# R210A.net
KiCad netlist of a schematic drawn in EAGLE
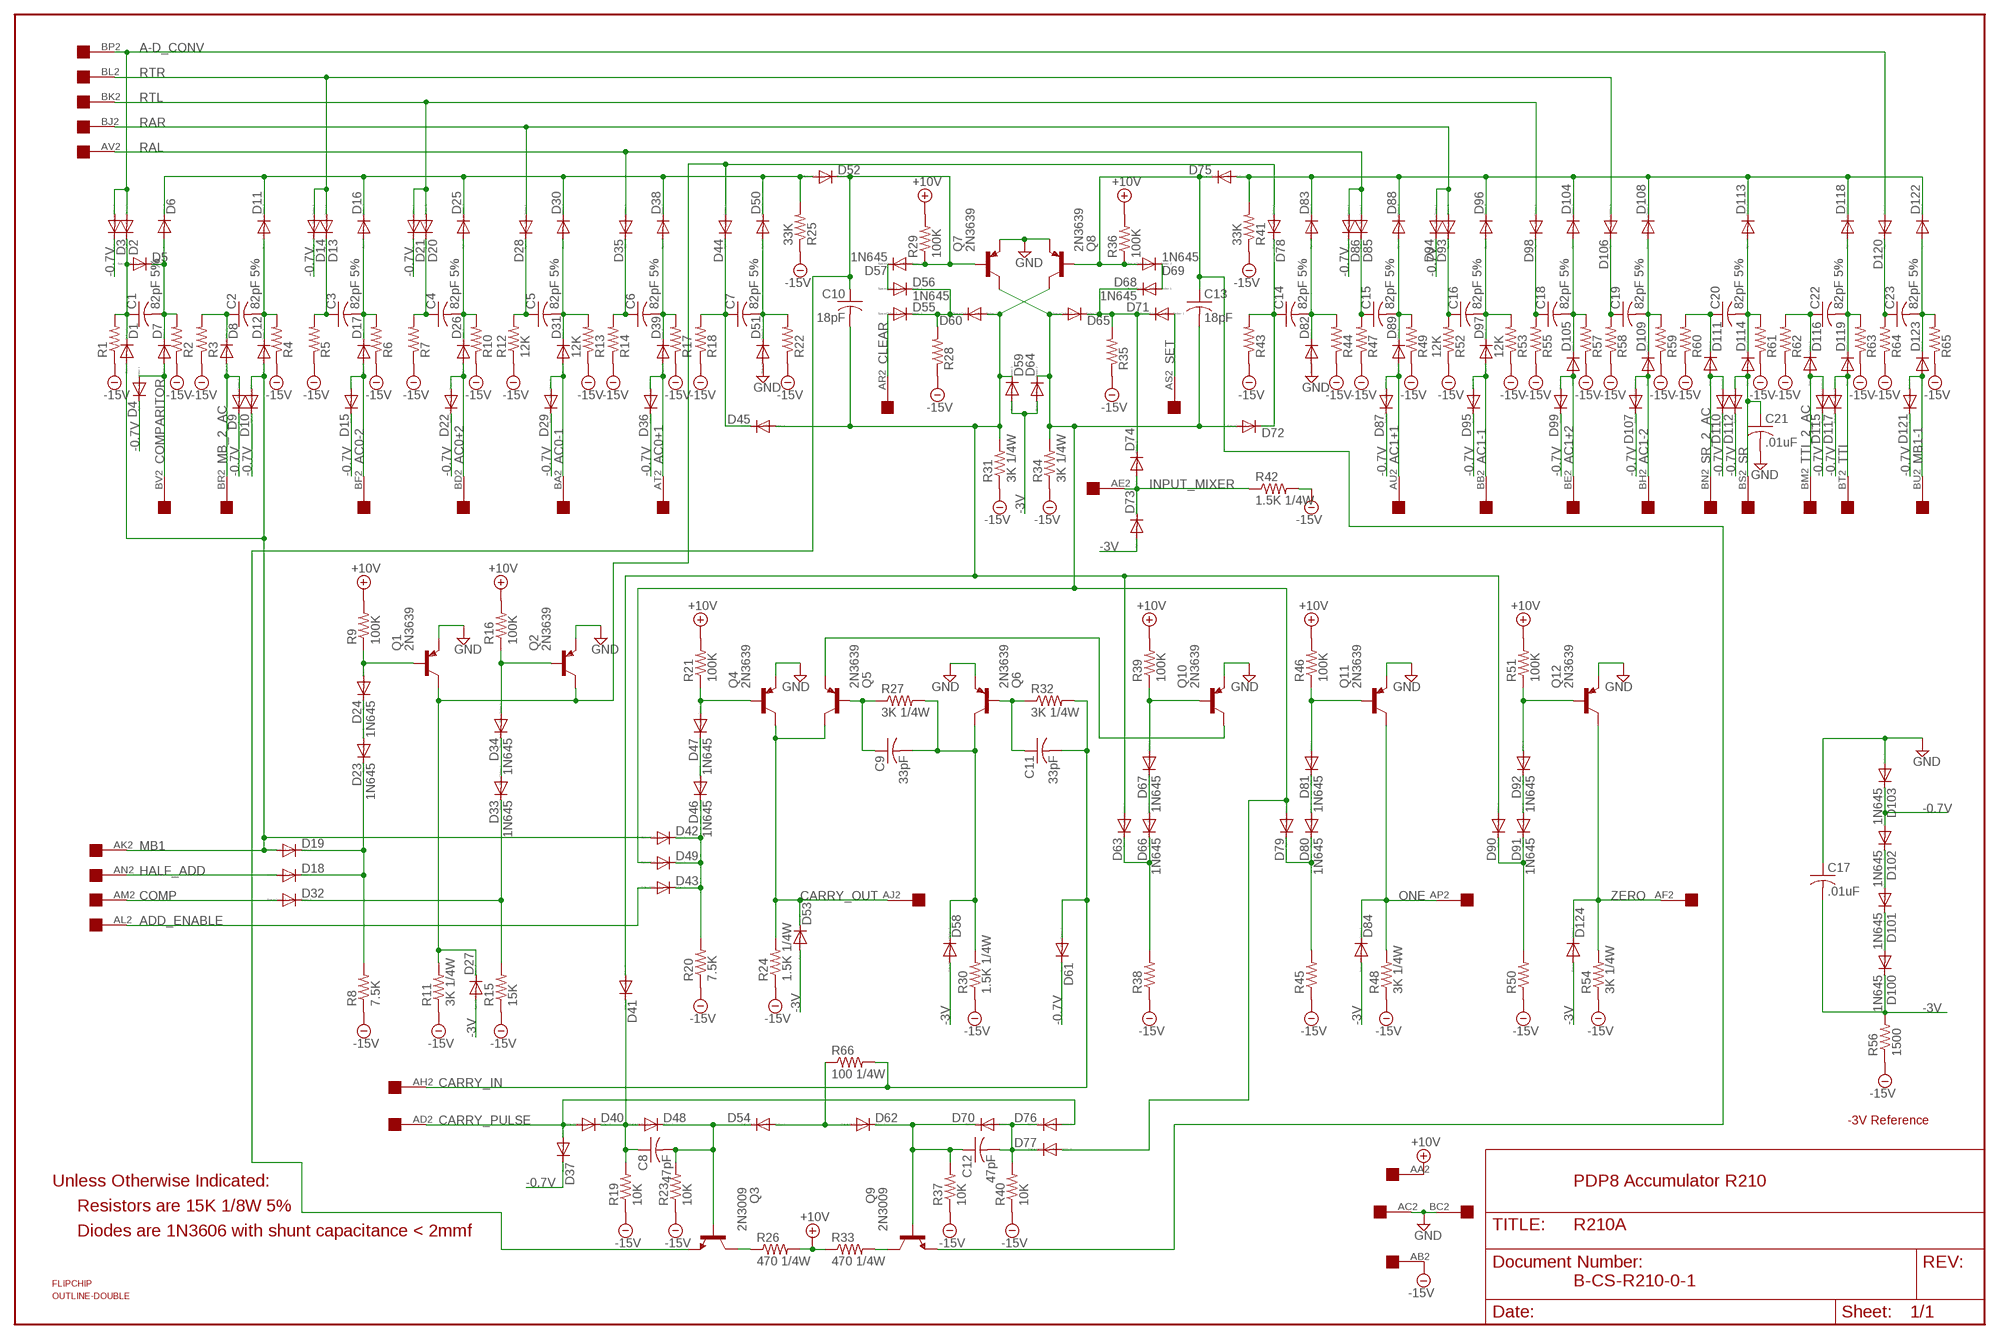
[diagram p0: schematic, sheet 1]

(export (version "E")
  (design (tool "Eeschema 10.0.6"))
  (components
    (comp (ref "C1")
      (value "82pF 5%")
      (footprint "eagle-import:C075-032X103")
      (libsource (lib "eagle-import") (part "C-US075-032X103"))
    )
    (comp (ref "C2")
      (value "82pF 5%")
      (footprint "eagle-import:C075-032X103")
      (libsource (lib "eagle-import") (part "C-US075-032X103"))
    )
    (comp (ref "C3")
      (value "82pF 5%")
      (footprint "eagle-import:C075-032X103")
      (libsource (lib "eagle-import") (part "C-US075-032X103"))
    )
    (comp (ref "C4")
      (value "82pF 5%")
      (footprint "eagle-import:C075-032X103")
      (libsource (lib "eagle-import") (part "C-US075-032X103"))
    )
    (comp (ref "C5")
      (value "82pF 5%")
      (footprint "eagle-import:C075-032X103")
      (libsource (lib "eagle-import") (part "C-US075-032X103"))
    )
    (comp (ref "C6")
      (value "82pF 5%")
      (footprint "eagle-import:C075-032X103")
      (libsource (lib "eagle-import") (part "C-US075-032X103"))
    )
    (comp (ref "C7")
      (value "82pF 5%")
      (footprint "eagle-import:C075-032X103")
      (libsource (lib "eagle-import") (part "C-US075-032X103"))
    )
    (comp (ref "C8")
      (value "47pF")
      (footprint "eagle-import:C075-032X103")
      (libsource (lib "eagle-import") (part "C-US075-032X103"))
    )
    (comp (ref "C9")
      (value "33pF")
      (footprint "eagle-import:C075-032X103")
      (libsource (lib "eagle-import") (part "C-US075-032X103"))
    )
    (comp (ref "C10")
      (value "18pF")
      (footprint "eagle-import:C075-032X103")
      (libsource (lib "eagle-import") (part "C-US075-032X103"))
    )
    (comp (ref "C11")
      (value "33pF")
      (footprint "eagle-import:C075-032X103")
      (libsource (lib "eagle-import") (part "C-US075-032X103"))
    )
    (comp (ref "C12")
      (value "47pF")
      (footprint "eagle-import:C075-032X103")
      (libsource (lib "eagle-import") (part "C-US075-032X103"))
    )
    (comp (ref "C13")
      (value "18pF")
      (footprint "eagle-import:C075-032X103")
      (libsource (lib "eagle-import") (part "C-US075-032X103"))
    )
    (comp (ref "C14")
      (value "82pF 5%")
      (footprint "eagle-import:C075-032X103")
      (libsource (lib "eagle-import") (part "C-US075-032X103"))
    )
    (comp (ref "C15")
      (value "82pF 5%")
      (footprint "eagle-import:C075-032X103")
      (libsource (lib "eagle-import") (part "C-US075-032X103"))
    )
    (comp (ref "C16")
      (value "82pF 5%")
      (footprint "eagle-import:C075-032X103")
      (libsource (lib "eagle-import") (part "C-US075-032X103"))
    )
    (comp (ref "C17")
      (value ".01uF")
      (footprint "eagle-import:C050-025X075")
      (libsource (lib "eagle-import") (part "C-US050-025X075"))
    )
    (comp (ref "C18")
      (value "82pF 5%")
      (footprint "eagle-import:C075-032X103")
      (libsource (lib "eagle-import") (part "C-US075-032X103"))
    )
    (comp (ref "C19")
      (value "82pF 5%")
      (footprint "eagle-import:C075-032X103")
      (libsource (lib "eagle-import") (part "C-US075-032X103"))
    )
    (comp (ref "C20")
      (value "82pF 5%")
      (footprint "eagle-import:C075-032X103")
      (libsource (lib "eagle-import") (part "C-US075-032X103"))
    )
    (comp (ref "C21")
      (value ".01uF")
      (footprint "eagle-import:C050-025X075")
      (libsource (lib "eagle-import") (part "C-US050-025X075"))
    )
    (comp (ref "C22")
      (value "82pF 5%")
      (footprint "eagle-import:C075-032X103")
      (libsource (lib "eagle-import") (part "C-US075-032X103"))
    )
    (comp (ref "C23")
      (value "82pF 5%")
      (footprint "eagle-import:C075-032X103")
      (libsource (lib "eagle-import") (part "C-US075-032X103"))
    )
    (comp (ref "D1")
      (value "1N4148DO35-10")
      (footprint "eagle-import:DO35-10")
      (libsource (lib "eagle-import") (part "1N4148DO35-10"))
    )
    (comp (ref "D2")
      (value "1N4148DO35-10")
      (footprint "eagle-import:DO35-10")
      (libsource (lib "eagle-import") (part "1N4148DO35-10"))
    )
    (comp (ref "D3")
      (value "1N4148DO35-10")
      (footprint "eagle-import:DO35-10")
      (libsource (lib "eagle-import") (part "1N4148DO35-10"))
    )
    (comp (ref "D4")
      (value "1N4148DO35-10")
      (footprint "eagle-import:DO35-10")
      (libsource (lib "eagle-import") (part "1N4148DO35-10"))
    )
    (comp (ref "D5")
      (value "1N4148DO35-10")
      (footprint "eagle-import:DO35-10")
      (libsource (lib "eagle-import") (part "1N4148DO35-10"))
    )
    (comp (ref "D6")
      (value "1N4148DO35-10")
      (footprint "eagle-import:DO35-10")
      (libsource (lib "eagle-import") (part "1N4148DO35-10"))
    )
    (comp (ref "D7")
      (value "1N4148DO35-10")
      (footprint "eagle-import:DO35-10")
      (libsource (lib "eagle-import") (part "1N4148DO35-10"))
    )
    (comp (ref "D8")
      (value "1N4148DO35-10")
      (footprint "eagle-import:DO35-10")
      (libsource (lib "eagle-import") (part "1N4148DO35-10"))
    )
    (comp (ref "D9")
      (value "1N4148DO35-10")
      (footprint "eagle-import:DO35-10")
      (libsource (lib "eagle-import") (part "1N4148DO35-10"))
    )
    (comp (ref "D10")
      (value "1N4148DO35-10")
      (footprint "eagle-import:DO35-10")
      (libsource (lib "eagle-import") (part "1N4148DO35-10"))
    )
    (comp (ref "D11")
      (value "1N4148DO35-10")
      (footprint "eagle-import:DO35-10")
      (libsource (lib "eagle-import") (part "1N4148DO35-10"))
    )
    (comp (ref "D12")
      (value "1N4148DO35-10")
      (footprint "eagle-import:DO35-10")
      (libsource (lib "eagle-import") (part "1N4148DO35-10"))
    )
    (comp (ref "D13")
      (value "1N4148DO35-10")
      (footprint "eagle-import:DO35-10")
      (libsource (lib "eagle-import") (part "1N4148DO35-10"))
    )
    (comp (ref "D14")
      (value "1N4148DO35-10")
      (footprint "eagle-import:DO35-10")
      (libsource (lib "eagle-import") (part "1N4148DO35-10"))
    )
    (comp (ref "D15")
      (value "1N4148DO35-10")
      (footprint "eagle-import:DO35-10")
      (libsource (lib "eagle-import") (part "1N4148DO35-10"))
    )
    (comp (ref "D16")
      (value "1N4148DO35-10")
      (footprint "eagle-import:DO35-10")
      (libsource (lib "eagle-import") (part "1N4148DO35-10"))
    )
    (comp (ref "D17")
      (value "1N4148DO35-10")
      (footprint "eagle-import:DO35-10")
      (libsource (lib "eagle-import") (part "1N4148DO35-10"))
    )
    (comp (ref "D18")
      (value "1N4148DO35-10")
      (footprint "eagle-import:DO35-10")
      (libsource (lib "eagle-import") (part "1N4148DO35-10"))
    )
    (comp (ref "D19")
      (value "1N4148DO35-10")
      (footprint "eagle-import:DO35-10")
      (libsource (lib "eagle-import") (part "1N4148DO35-10"))
    )
    (comp (ref "D20")
      (value "1N4148DO35-10")
      (footprint "eagle-import:DO35-10")
      (libsource (lib "eagle-import") (part "1N4148DO35-10"))
    )
    (comp (ref "D21")
      (value "1N4148DO35-10")
      (footprint "eagle-import:DO35-10")
      (libsource (lib "eagle-import") (part "1N4148DO35-10"))
    )
    (comp (ref "D22")
      (value "1N4148DO35-10")
      (footprint "eagle-import:DO35-10")
      (libsource (lib "eagle-import") (part "1N4148DO35-10"))
    )
    (comp (ref "D23")
      (value "1N645")
      (footprint "eagle-import:DO35-10")
      (libsource (lib "eagle-import") (part "1N4148DO35-10"))
    )
    (comp (ref "D24")
      (value "1N645")
      (footprint "eagle-import:DO35-10")
      (libsource (lib "eagle-import") (part "1N4148DO35-10"))
    )
    (comp (ref "D25")
      (value "1N4148DO35-10")
      (footprint "eagle-import:DO35-10")
      (libsource (lib "eagle-import") (part "1N4148DO35-10"))
    )
    (comp (ref "D26")
      (value "1N4148DO35-10")
      (footprint "eagle-import:DO35-10")
      (libsource (lib "eagle-import") (part "1N4148DO35-10"))
    )
    (comp (ref "D27")
      (value "1N4148DO35-10")
      (footprint "eagle-import:DO35-10")
      (libsource (lib "eagle-import") (part "1N4148DO35-10"))
    )
    (comp (ref "D28")
      (value "1N4148DO35-10")
      (footprint "eagle-import:DO35-10")
      (libsource (lib "eagle-import") (part "1N4148DO35-10"))
    )
    (comp (ref "D29")
      (value "1N4148DO35-10")
      (footprint "eagle-import:DO35-10")
      (libsource (lib "eagle-import") (part "1N4148DO35-10"))
    )
    (comp (ref "D30")
      (value "1N4148DO35-10")
      (footprint "eagle-import:DO35-10")
      (libsource (lib "eagle-import") (part "1N4148DO35-10"))
    )
    (comp (ref "D31")
      (value "1N4148DO35-10")
      (footprint "eagle-import:DO35-10")
      (libsource (lib "eagle-import") (part "1N4148DO35-10"))
    )
    (comp (ref "D32")
      (value "1N4148DO35-10")
      (footprint "eagle-import:DO35-10")
      (libsource (lib "eagle-import") (part "1N4148DO35-10"))
    )
    (comp (ref "D33")
      (value "1N645")
      (footprint "eagle-import:DO35-10")
      (libsource (lib "eagle-import") (part "1N4148DO35-10"))
    )
    (comp (ref "D34")
      (value "1N645")
      (footprint "eagle-import:DO35-10")
      (libsource (lib "eagle-import") (part "1N4148DO35-10"))
    )
    (comp (ref "D35")
      (value "1N4148DO35-10")
      (footprint "eagle-import:DO35-10")
      (libsource (lib "eagle-import") (part "1N4148DO35-10"))
    )
    (comp (ref "D36")
      (value "1N4148DO35-10")
      (footprint "eagle-import:DO35-10")
      (libsource (lib "eagle-import") (part "1N4148DO35-10"))
    )
    (comp (ref "D37")
      (value "1N4148DO35-10")
      (footprint "eagle-import:DO35-10")
      (libsource (lib "eagle-import") (part "1N4148DO35-10"))
    )
    (comp (ref "D38")
      (value "1N4148DO35-10")
      (footprint "eagle-import:DO35-10")
      (libsource (lib "eagle-import") (part "1N4148DO35-10"))
    )
    (comp (ref "D39")
      (value "1N4148DO35-10")
      (footprint "eagle-import:DO35-10")
      (libsource (lib "eagle-import") (part "1N4148DO35-10"))
    )
    (comp (ref "D40")
      (value "1N4148DO35-10")
      (footprint "eagle-import:DO35-10")
      (libsource (lib "eagle-import") (part "1N4148DO35-10"))
    )
    (comp (ref "D41")
      (value "1N4148DO35-10")
      (footprint "eagle-import:DO35-10")
      (libsource (lib "eagle-import") (part "1N4148DO35-10"))
    )
    (comp (ref "D42")
      (value "1N4148DO35-10")
      (footprint "eagle-import:DO35-10")
      (libsource (lib "eagle-import") (part "1N4148DO35-10"))
    )
    (comp (ref "D43")
      (value "1N4148DO35-10")
      (footprint "eagle-import:DO35-10")
      (libsource (lib "eagle-import") (part "1N4148DO35-10"))
    )
    (comp (ref "D44")
      (value "1N4148DO35-10")
      (footprint "eagle-import:DO35-10")
      (libsource (lib "eagle-import") (part "1N4148DO35-10"))
    )
    (comp (ref "D45")
      (value "1N4148DO35-10")
      (footprint "eagle-import:DO35-10")
      (libsource (lib "eagle-import") (part "1N4148DO35-10"))
    )
    (comp (ref "D46")
      (value "1N645")
      (footprint "eagle-import:DO35-10")
      (libsource (lib "eagle-import") (part "1N4148DO35-10"))
    )
    (comp (ref "D47")
      (value "1N645")
      (footprint "eagle-import:DO35-10")
      (libsource (lib "eagle-import") (part "1N4148DO35-10"))
    )
    (comp (ref "D48")
      (value "1N4148DO35-10")
      (footprint "eagle-import:DO35-10")
      (libsource (lib "eagle-import") (part "1N4148DO35-10"))
    )
    (comp (ref "D49")
      (value "1N4148DO35-10")
      (footprint "eagle-import:DO35-10")
      (libsource (lib "eagle-import") (part "1N4148DO35-10"))
    )
    (comp (ref "D50")
      (value "1N4148DO35-10")
      (footprint "eagle-import:DO35-10")
      (libsource (lib "eagle-import") (part "1N4148DO35-10"))
    )
    (comp (ref "D51")
      (value "1N4148DO35-10")
      (footprint "eagle-import:DO35-10")
      (libsource (lib "eagle-import") (part "1N4148DO35-10"))
    )
    (comp (ref "D52")
      (value "1N4148DO35-10")
      (footprint "eagle-import:DO35-10")
      (libsource (lib "eagle-import") (part "1N4148DO35-10"))
    )
    (comp (ref "D53")
      (value "1N4148DO35-10")
      (footprint "eagle-import:DO35-10")
      (libsource (lib "eagle-import") (part "1N4148DO35-10"))
    )
    (comp (ref "D54")
      (value "1N4148DO35-10")
      (footprint "eagle-import:DO35-10")
      (libsource (lib "eagle-import") (part "1N4148DO35-10"))
    )
    (comp (ref "D55")
      (value "1N4148DO35-10")
      (footprint "eagle-import:DO35-10")
      (libsource (lib "eagle-import") (part "1N4148DO35-10"))
    )
    (comp (ref "D56")
      (value "1N645")
      (footprint "eagle-import:DO35-10")
      (libsource (lib "eagle-import") (part "1N4148DO35-10"))
    )
    (comp (ref "D57")
      (value "1N645")
      (footprint "eagle-import:DO35-10")
      (libsource (lib "eagle-import") (part "1N4148DO35-10"))
    )
    (comp (ref "D58")
      (value "1N4148DO35-10")
      (footprint "eagle-import:DO35-10")
      (libsource (lib "eagle-import") (part "1N4148DO35-10"))
    )
    (comp (ref "D59")
      (value "1N4148DO35-10")
      (footprint "eagle-import:DO35-10")
      (libsource (lib "eagle-import") (part "1N4148DO35-10"))
    )
    (comp (ref "D60")
      (value "1N4148DO35-10")
      (footprint "eagle-import:DO35-10")
      (libsource (lib "eagle-import") (part "1N4148DO35-10"))
    )
    (comp (ref "D61")
      (value "1N4148DO35-10")
      (footprint "eagle-import:DO35-10")
      (libsource (lib "eagle-import") (part "1N4148DO35-10"))
    )
    (comp (ref "D62")
      (value "1N4148DO35-10")
      (footprint "eagle-import:DO35-10")
      (libsource (lib "eagle-import") (part "1N4148DO35-10"))
    )
    (comp (ref "D63")
      (value "1N4148DO35-10")
      (footprint "eagle-import:DO35-10")
      (libsource (lib "eagle-import") (part "1N4148DO35-10"))
    )
    (comp (ref "D64")
      (value "1N4148DO35-10")
      (footprint "eagle-import:DO35-10")
      (libsource (lib "eagle-import") (part "1N4148DO35-10"))
    )
    (comp (ref "D65")
      (value "1N4148DO35-10")
      (footprint "eagle-import:DO35-10")
      (libsource (lib "eagle-import") (part "1N4148DO35-10"))
    )
    (comp (ref "D66")
      (value "1N645")
      (footprint "eagle-import:DO35-10")
      (libsource (lib "eagle-import") (part "1N4148DO35-10"))
    )
    (comp (ref "D67")
      (value "1N645")
      (footprint "eagle-import:DO35-10")
      (libsource (lib "eagle-import") (part "1N4148DO35-10"))
    )
    (comp (ref "D68")
      (value "1N645")
      (footprint "eagle-import:DO35-10")
      (libsource (lib "eagle-import") (part "1N4148DO35-10"))
    )
    (comp (ref "D69")
      (value "1N645")
      (footprint "eagle-import:DO35-10")
      (libsource (lib "eagle-import") (part "1N4148DO35-10"))
    )
    (comp (ref "D70")
      (value "1N4148DO35-10")
      (footprint "eagle-import:DO35-10")
      (libsource (lib "eagle-import") (part "1N4148DO35-10"))
    )
    (comp (ref "D71")
      (value "1N4148DO35-10")
      (footprint "eagle-import:DO35-10")
      (libsource (lib "eagle-import") (part "1N4148DO35-10"))
    )
    (comp (ref "D72")
      (value "1N4148DO35-10")
      (footprint "eagle-import:DO35-10")
      (libsource (lib "eagle-import") (part "1N4148DO35-10"))
    )
    (comp (ref "D73")
      (value "1N4148DO35-10")
      (footprint "eagle-import:DO35-10")
      (libsource (lib "eagle-import") (part "1N4148DO35-10"))
    )
    (comp (ref "D74")
      (value "1N4148DO35-10")
      (footprint "eagle-import:DO35-10")
      (libsource (lib "eagle-import") (part "1N4148DO35-10"))
    )
    (comp (ref "D75")
      (value "1N4148DO35-10")
      (footprint "eagle-import:DO35-10")
      (libsource (lib "eagle-import") (part "1N4148DO35-10"))
    )
    (comp (ref "D76")
      (value "1N4148DO35-10")
      (footprint "eagle-import:DO35-10")
      (libsource (lib "eagle-import") (part "1N4148DO35-10"))
    )
    (comp (ref "D77")
      (value "1N4148DO35-10")
      (footprint "eagle-import:DO35-10")
      (libsource (lib "eagle-import") (part "1N4148DO35-10"))
    )
    (comp (ref "D78")
      (value "1N4148DO35-10")
      (footprint "eagle-import:DO35-10")
      (libsource (lib "eagle-import") (part "1N4148DO35-10"))
    )
    (comp (ref "D79")
      (value "1N4148DO35-10")
      (footprint "eagle-import:DO35-10")
      (libsource (lib "eagle-import") (part "1N4148DO35-10"))
    )
    (comp (ref "D80")
      (value "1N645")
      (footprint "eagle-import:DO35-10")
      (libsource (lib "eagle-import") (part "1N4148DO35-10"))
    )
    (comp (ref "D81")
      (value "1N645")
      (footprint "eagle-import:DO35-10")
      (libsource (lib "eagle-import") (part "1N4148DO35-10"))
    )
    (comp (ref "D82")
      (value "1N4148DO35-10")
      (footprint "eagle-import:DO35-10")
      (libsource (lib "eagle-import") (part "1N4148DO35-10"))
    )
    (comp (ref "D83")
      (value "1N4148DO35-10")
      (footprint "eagle-import:DO35-10")
      (libsource (lib "eagle-import") (part "1N4148DO35-10"))
    )
    (comp (ref "D84")
      (value "1N4148DO35-10")
      (footprint "eagle-import:DO35-10")
      (libsource (lib "eagle-import") (part "1N4148DO35-10"))
    )
    (comp (ref "D85")
      (value "1N4148DO35-10")
      (footprint "eagle-import:DO35-10")
      (libsource (lib "eagle-import") (part "1N4148DO35-10"))
    )
    (comp (ref "D86")
      (value "1N4148DO35-10")
      (footprint "eagle-import:DO35-10")
      (libsource (lib "eagle-import") (part "1N4148DO35-10"))
    )
    (comp (ref "D87")
      (value "1N4148DO35-10")
      (footprint "eagle-import:DO35-10")
      (libsource (lib "eagle-import") (part "1N4148DO35-10"))
    )
    (comp (ref "D88")
      (value "1N4148DO35-10")
      (footprint "eagle-import:DO35-10")
      (libsource (lib "eagle-import") (part "1N4148DO35-10"))
    )
    (comp (ref "D89")
      (value "1N4148DO35-10")
      (footprint "eagle-import:DO35-10")
      (libsource (lib "eagle-import") (part "1N4148DO35-10"))
    )
    (comp (ref "D90")
      (value "1N4148DO35-10")
      (footprint "eagle-import:DO35-10")
      (libsource (lib "eagle-import") (part "1N4148DO35-10"))
    )
    (comp (ref "D91")
      (value "1N645")
      (footprint "eagle-import:DO35-10")
      (libsource (lib "eagle-import") (part "1N4148DO35-10"))
    )
    (comp (ref "D92")
      (value "1N645")
      (footprint "eagle-import:DO35-10")
      (libsource (lib "eagle-import") (part "1N4148DO35-10"))
    )
    (comp (ref "D93")
      (value "1N4148DO35-10")
      (footprint "eagle-import:DO35-10")
      (libsource (lib "eagle-import") (part "1N4148DO35-10"))
    )
    (comp (ref "D94")
      (value "1N4148DO35-10")
      (footprint "eagle-import:DO35-10")
      (libsource (lib "eagle-import") (part "1N4148DO35-10"))
    )
    (comp (ref "D95")
      (value "1N4148DO35-10")
      (footprint "eagle-import:DO35-10")
      (libsource (lib "eagle-import") (part "1N4148DO35-10"))
    )
    (comp (ref "D96")
      (value "1N4148DO35-10")
      (footprint "eagle-import:DO35-10")
      (libsource (lib "eagle-import") (part "1N4148DO35-10"))
    )
    (comp (ref "D97")
      (value "1N4148DO35-10")
      (footprint "eagle-import:DO35-10")
      (libsource (lib "eagle-import") (part "1N4148DO35-10"))
    )
    (comp (ref "D98")
      (value "1N4148DO35-10")
      (footprint "eagle-import:DO35-10")
      (libsource (lib "eagle-import") (part "1N4148DO35-10"))
    )
    (comp (ref "D99")
      (value "1N4148DO35-10")
      (footprint "eagle-import:DO35-10")
      (libsource (lib "eagle-import") (part "1N4148DO35-10"))
    )
    (comp (ref "D100")
      (value "1N645")
      (footprint "eagle-import:DO35-10")
      (libsource (lib "eagle-import") (part "1N4148DO35-10"))
    )
    (comp (ref "D101")
      (value "1N645")
      (footprint "eagle-import:DO35-10")
      (libsource (lib "eagle-import") (part "1N4148DO35-10"))
    )
    (comp (ref "D102")
      (value "1N645")
      (footprint "eagle-import:DO35-10")
      (libsource (lib "eagle-import") (part "1N4148DO35-10"))
    )
    (comp (ref "D103")
      (value "1N645")
      (footprint "eagle-import:DO35-10")
      (libsource (lib "eagle-import") (part "1N4148DO35-10"))
    )
    (comp (ref "D104")
      (value "1N4148DO35-10")
      (footprint "eagle-import:DO35-10")
      (libsource (lib "eagle-import") (part "1N4148DO35-10"))
    )
    (comp (ref "D105")
      (value "1N4148DO35-10")
      (footprint "eagle-import:DO35-10")
      (libsource (lib "eagle-import") (part "1N4148DO35-10"))
    )
    (comp (ref "D106")
      (value "1N4148DO35-10")
      (footprint "eagle-import:DO35-10")
      (libsource (lib "eagle-import") (part "1N4148DO35-10"))
    )
    (comp (ref "D107")
      (value "1N4148DO35-10")
      (footprint "eagle-import:DO35-10")
      (libsource (lib "eagle-import") (part "1N4148DO35-10"))
    )
    (comp (ref "D108")
      (value "1N4148DO35-10")
      (footprint "eagle-import:DO35-10")
      (libsource (lib "eagle-import") (part "1N4148DO35-10"))
    )
    (comp (ref "D109")
      (value "1N4148DO35-10")
      (footprint "eagle-import:DO35-10")
      (libsource (lib "eagle-import") (part "1N4148DO35-10"))
    )
    (comp (ref "D110")
      (value "1N4148DO35-10")
      (footprint "eagle-import:DO35-10")
      (libsource (lib "eagle-import") (part "1N4148DO35-10"))
    )
    (comp (ref "D111")
      (value "1N4148DO35-10")
      (footprint "eagle-import:DO35-10")
      (libsource (lib "eagle-import") (part "1N4148DO35-10"))
    )
    (comp (ref "D112")
      (value "1N4148DO35-10")
      (footprint "eagle-import:DO35-10")
      (libsource (lib "eagle-import") (part "1N4148DO35-10"))
    )
    (comp (ref "D113")
      (value "1N4148DO35-10")
      (footprint "eagle-import:DO35-10")
      (libsource (lib "eagle-import") (part "1N4148DO35-10"))
    )
    (comp (ref "D114")
      (value "1N4148DO35-10")
      (footprint "eagle-import:DO35-10")
      (libsource (lib "eagle-import") (part "1N4148DO35-10"))
    )
    (comp (ref "D115")
      (value "1N4148DO35-10")
      (footprint "eagle-import:DO35-10")
      (libsource (lib "eagle-import") (part "1N4148DO35-10"))
    )
    (comp (ref "D116")
      (value "1N4148DO35-10")
      (footprint "eagle-import:DO35-10")
      (libsource (lib "eagle-import") (part "1N4148DO35-10"))
    )
    (comp (ref "D117")
      (value "1N4148DO35-10")
      (footprint "eagle-import:DO35-10")
      (libsource (lib "eagle-import") (part "1N4148DO35-10"))
    )
    (comp (ref "D118")
      (value "1N4148DO35-10")
      (footprint "eagle-import:DO35-10")
      (libsource (lib "eagle-import") (part "1N4148DO35-10"))
    )
    (comp (ref "D119")
      (value "1N4148DO35-10")
      (footprint "eagle-import:DO35-10")
      (libsource (lib "eagle-import") (part "1N4148DO35-10"))
    )
    (comp (ref "D120")
      (value "1N4148DO35-10")
      (footprint "eagle-import:DO35-10")
      (libsource (lib "eagle-import") (part "1N4148DO35-10"))
    )
    (comp (ref "D121")
      (value "1N4148DO35-10")
      (footprint "eagle-import:DO35-10")
      (libsource (lib "eagle-import") (part "1N4148DO35-10"))
    )
    (comp (ref "D122")
      (value "1N4148DO35-10")
      (footprint "eagle-import:DO35-10")
      (libsource (lib "eagle-import") (part "1N4148DO35-10"))
    )
    (comp (ref "D123")
      (value "1N4148DO35-10")
      (footprint "eagle-import:DO35-10")
      (libsource (lib "eagle-import") (part "1N4148DO35-10"))
    )
    (comp (ref "D124")
      (value "1N4148DO35-10")
      (footprint "eagle-import:DO35-10")
      (libsource (lib "eagle-import") (part "1N4148DO35-10"))
    )
    (comp (ref "Q1")
      (value "2N3639")
      (footprint "eagle-import:TO39")
      (libsource (lib "eagle-import") (part "2N3637"))
    )
    (comp (ref "Q2")
      (value "2N3639")
      (footprint "eagle-import:TO39")
      (libsource (lib "eagle-import") (part "2N3637"))
    )
    (comp (ref "Q3")
      (value "2N3009")
      (footprint "eagle-import:TO5")
      (libsource (lib "eagle-import") (part "2N2102"))
    )
    (comp (ref "Q4")
      (value "2N3639")
      (footprint "eagle-import:TO39")
      (libsource (lib "eagle-import") (part "2N3637"))
    )
    (comp (ref "Q5")
      (value "2N3639")
      (footprint "eagle-import:TO39")
      (libsource (lib "eagle-import") (part "2N3637"))
    )
    (comp (ref "Q6")
      (value "2N3639")
      (footprint "eagle-import:TO39")
      (libsource (lib "eagle-import") (part "2N3637"))
    )
    (comp (ref "Q7")
      (value "2N3639")
      (footprint "eagle-import:TO39")
      (libsource (lib "eagle-import") (part "2N3637"))
    )
    (comp (ref "Q8")
      (value "2N3639")
      (footprint "eagle-import:TO39")
      (libsource (lib "eagle-import") (part "2N3637"))
    )
    (comp (ref "Q9")
      (value "2N3009")
      (footprint "eagle-import:TO5")
      (libsource (lib "eagle-import") (part "2N2102"))
    )
    (comp (ref "Q10")
      (value "2N3639")
      (footprint "eagle-import:TO39")
      (libsource (lib "eagle-import") (part "2N3637"))
    )
    (comp (ref "Q11")
      (value "2N3639")
      (footprint "eagle-import:TO39")
      (libsource (lib "eagle-import") (part "2N3637"))
    )
    (comp (ref "Q12")
      (value "2N3639")
      (footprint "eagle-import:TO39")
      (libsource (lib "eagle-import") (part "2N3637"))
    )
    (comp (ref "R1")
      (value "R-US_0207/10")
      (footprint "eagle-import:0207_10")
      (libsource (lib "eagle-import") (part "R-US_0207/10"))
    )
    (comp (ref "R2")
      (value "R-US_0207/10")
      (footprint "eagle-import:0207_10")
      (libsource (lib "eagle-import") (part "R-US_0207/10"))
    )
    (comp (ref "R3")
      (value "R-US_0207/10")
      (footprint "eagle-import:0207_10")
      (libsource (lib "eagle-import") (part "R-US_0207/10"))
    )
    (comp (ref "R4")
      (value "R-US_0207/10")
      (footprint "eagle-import:0207_10")
      (libsource (lib "eagle-import") (part "R-US_0207/10"))
    )
    (comp (ref "R5")
      (value "R-US_0207/10")
      (footprint "eagle-import:0207_10")
      (libsource (lib "eagle-import") (part "R-US_0207/10"))
    )
    (comp (ref "R6")
      (value "R-US_0207/10")
      (footprint "eagle-import:0207_10")
      (libsource (lib "eagle-import") (part "R-US_0207/10"))
    )
    (comp (ref "R7")
      (value "R-US_0207/10")
      (footprint "eagle-import:0207_10")
      (libsource (lib "eagle-import") (part "R-US_0207/10"))
    )
    (comp (ref "R8")
      (value "7.5K")
      (footprint "eagle-import:0207_10")
      (libsource (lib "eagle-import") (part "R-US_0207/10"))
    )
    (comp (ref "R9")
      (value "100K")
      (footprint "eagle-import:0207_10")
      (libsource (lib "eagle-import") (part "R-US_0207/10"))
    )
    (comp (ref "R10")
      (value "R-US_0207/10")
      (footprint "eagle-import:0207_10")
      (libsource (lib "eagle-import") (part "R-US_0207/10"))
    )
    (comp (ref "R11")
      (value "3K 1/4W")
      (footprint "eagle-import:0207_10")
      (libsource (lib "eagle-import") (part "R-US_0207/10"))
    )
    (comp (ref "R12")
      (value "12K")
      (footprint "eagle-import:0207_10")
      (libsource (lib "eagle-import") (part "R-US_0207/10"))
    )
    (comp (ref "R13")
      (value "12K")
      (footprint "eagle-import:0207_10")
      (libsource (lib "eagle-import") (part "R-US_0207/10"))
    )
    (comp (ref "R14")
      (value "R-US_0207/10")
      (footprint "eagle-import:0207_10")
      (libsource (lib "eagle-import") (part "R-US_0207/10"))
    )
    (comp (ref "R15")
      (value "15K")
      (footprint "eagle-import:0207_10")
      (libsource (lib "eagle-import") (part "R-US_0207/10"))
    )
    (comp (ref "R16")
      (value "100K")
      (footprint "eagle-import:0207_10")
      (libsource (lib "eagle-import") (part "R-US_0207/10"))
    )
    (comp (ref "R17")
      (value "R-US_0207/10")
      (footprint "eagle-import:0207_10")
      (libsource (lib "eagle-import") (part "R-US_0207/10"))
    )
    (comp (ref "R18")
      (value "R-US_0207/10")
      (footprint "eagle-import:0207_10")
      (libsource (lib "eagle-import") (part "R-US_0207/10"))
    )
    (comp (ref "R19")
      (value "10K")
      (footprint "eagle-import:0207_10")
      (libsource (lib "eagle-import") (part "R-US_0207/10"))
    )
    (comp (ref "R20")
      (value "7.5K")
      (footprint "eagle-import:0207_10")
      (libsource (lib "eagle-import") (part "R-US_0207/10"))
    )
    (comp (ref "R21")
      (value "100K")
      (footprint "eagle-import:0207_10")
      (libsource (lib "eagle-import") (part "R-US_0207/10"))
    )
    (comp (ref "R22")
      (value "R-US_0207/10")
      (footprint "eagle-import:0207_10")
      (libsource (lib "eagle-import") (part "R-US_0207/10"))
    )
    (comp (ref "R23")
      (value "10K")
      (footprint "eagle-import:0207_10")
      (libsource (lib "eagle-import") (part "R-US_0207/10"))
    )
    (comp (ref "R24")
      (value "1.5K 1/4W")
      (footprint "eagle-import:0207_10")
      (libsource (lib "eagle-import") (part "R-US_0207/10"))
    )
    (comp (ref "R25")
      (value "33K")
      (footprint "eagle-import:0207_10")
      (libsource (lib "eagle-import") (part "R-US_0207/10"))
    )
    (comp (ref "R26")
      (value "470 1/4W")
      (footprint "eagle-import:0207_10")
      (libsource (lib "eagle-import") (part "R-US_0207/10"))
    )
    (comp (ref "R27")
      (value "3K 1/4W")
      (footprint "eagle-import:0207_10")
      (libsource (lib "eagle-import") (part "R-US_0207/10"))
    )
    (comp (ref "R28")
      (value "R-US_0207/10")
      (footprint "eagle-import:0207_10")
      (libsource (lib "eagle-import") (part "R-US_0207/10"))
    )
    (comp (ref "R29")
      (value "100K")
      (footprint "eagle-import:0207_10")
      (libsource (lib "eagle-import") (part "R-US_0207/10"))
    )
    (comp (ref "R30")
      (value "1.5K 1/4W")
      (footprint "eagle-import:0207_10")
      (libsource (lib "eagle-import") (part "R-US_0207/10"))
    )
    (comp (ref "R31")
      (value "3K 1/4W")
      (footprint "eagle-import:0207_10")
      (libsource (lib "eagle-import") (part "R-US_0207/10"))
    )
    (comp (ref "R32")
      (value "3K 1/4W")
      (footprint "eagle-import:0207_10")
      (libsource (lib "eagle-import") (part "R-US_0207/10"))
    )
    (comp (ref "R33")
      (value "470 1/4W")
      (footprint "eagle-import:0207_10")
      (libsource (lib "eagle-import") (part "R-US_0207/10"))
    )
    (comp (ref "R34")
      (value "3K 1/4W")
      (footprint "eagle-import:0207_10")
      (libsource (lib "eagle-import") (part "R-US_0207/10"))
    )
    (comp (ref "R35")
      (value "R-US_0207/10")
      (footprint "eagle-import:0207_10")
      (libsource (lib "eagle-import") (part "R-US_0207/10"))
    )
    (comp (ref "R36")
      (value "100K")
      (footprint "eagle-import:0207_10")
      (libsource (lib "eagle-import") (part "R-US_0207/10"))
    )
    (comp (ref "R37")
      (value "10K")
      (footprint "eagle-import:0207_10")
      (libsource (lib "eagle-import") (part "R-US_0207/10"))
    )
    (comp (ref "R38")
      (value "R-US_0207/10")
      (footprint "eagle-import:0207_10")
      (libsource (lib "eagle-import") (part "R-US_0207/10"))
    )
    (comp (ref "R39")
      (value "100K")
      (footprint "eagle-import:0207_10")
      (libsource (lib "eagle-import") (part "R-US_0207/10"))
    )
    (comp (ref "R40")
      (value "10K")
      (footprint "eagle-import:0207_10")
      (libsource (lib "eagle-import") (part "R-US_0207/10"))
    )
    (comp (ref "R41")
      (value "33K")
      (footprint "eagle-import:0207_10")
      (libsource (lib "eagle-import") (part "R-US_0207/10"))
    )
    (comp (ref "R42")
      (value "1.5K 1/4W")
      (footprint "eagle-import:0207_10")
      (libsource (lib "eagle-import") (part "R-US_0207/10"))
    )
    (comp (ref "R43")
      (value "R-US_0207/10")
      (footprint "eagle-import:0207_10")
      (libsource (lib "eagle-import") (part "R-US_0207/10"))
    )
    (comp (ref "R44")
      (value "R-US_0207/10")
      (footprint "eagle-import:0207_10")
      (libsource (lib "eagle-import") (part "R-US_0207/10"))
    )
    (comp (ref "R45")
      (value "R-US_0207/10")
      (footprint "eagle-import:0207_10")
      (libsource (lib "eagle-import") (part "R-US_0207/10"))
    )
    (comp (ref "R46")
      (value "100K")
      (footprint "eagle-import:0207_10")
      (libsource (lib "eagle-import") (part "R-US_0207/10"))
    )
    (comp (ref "R47")
      (value "R-US_0207/10")
      (footprint "eagle-import:0207_10")
      (libsource (lib "eagle-import") (part "R-US_0207/10"))
    )
    (comp (ref "R48")
      (value "3K 1/4W")
      (footprint "eagle-import:0207_10")
      (libsource (lib "eagle-import") (part "R-US_0207/10"))
    )
    (comp (ref "R49")
      (value "R-US_0207/10")
      (footprint "eagle-import:0207_10")
      (libsource (lib "eagle-import") (part "R-US_0207/10"))
    )
    (comp (ref "R50")
      (value "R-US_0207/10")
      (footprint "eagle-import:0207_10")
      (libsource (lib "eagle-import") (part "R-US_0207/10"))
    )
    (comp (ref "R51")
      (value "100K")
      (footprint "eagle-import:0207_10")
      (libsource (lib "eagle-import") (part "R-US_0207/10"))
    )
    (comp (ref "R52")
      (value "12K")
      (footprint "eagle-import:0207_10")
      (libsource (lib "eagle-import") (part "R-US_0207/10"))
    )
    (comp (ref "R53")
      (value "12K")
      (footprint "eagle-import:0207_10")
      (libsource (lib "eagle-import") (part "R-US_0207/10"))
    )
    (comp (ref "R54")
      (value "3K 1/4W")
      (footprint "eagle-import:0207_10")
      (libsource (lib "eagle-import") (part "R-US_0207/10"))
    )
    (comp (ref "R55")
      (value "R-US_0207/10")
      (footprint "eagle-import:0207_10")
      (libsource (lib "eagle-import") (part "R-US_0207/10"))
    )
    (comp (ref "R56")
      (value "1500")
      (footprint "eagle-import:0207_10")
      (libsource (lib "eagle-import") (part "R-US_0207/10"))
    )
    (comp (ref "R57")
      (value "R-US_0207/10")
      (footprint "eagle-import:0207_10")
      (libsource (lib "eagle-import") (part "R-US_0207/10"))
    )
    (comp (ref "R58")
      (value "R-US_0207/10")
      (footprint "eagle-import:0207_10")
      (libsource (lib "eagle-import") (part "R-US_0207/10"))
    )
    (comp (ref "R59")
      (value "R-US_0207/10")
      (footprint "eagle-import:0207_10")
      (libsource (lib "eagle-import") (part "R-US_0207/10"))
    )
    (comp (ref "R60")
      (value "R-US_0207/10")
      (footprint "eagle-import:0207_10")
      (libsource (lib "eagle-import") (part "R-US_0207/10"))
    )
    (comp (ref "R61")
      (value "R-US_0207/10")
      (footprint "eagle-import:0207_10")
      (libsource (lib "eagle-import") (part "R-US_0207/10"))
    )
    (comp (ref "R62")
      (value "R-US_0207/10")
      (footprint "eagle-import:0207_10")
      (libsource (lib "eagle-import") (part "R-US_0207/10"))
    )
    (comp (ref "R63")
      (value "R-US_0207/10")
      (footprint "eagle-import:0207_10")
      (libsource (lib "eagle-import") (part "R-US_0207/10"))
    )
    (comp (ref "R64")
      (value "R-US_0207/10")
      (footprint "eagle-import:0207_10")
      (libsource (lib "eagle-import") (part "R-US_0207/10"))
    )
    (comp (ref "R65")
      (value "R-US_0207/10")
      (footprint "eagle-import:0207_10")
      (libsource (lib "eagle-import") (part "R-US_0207/10"))
    )
    (comp (ref "R66")
      (value "100 1/4W")
      (footprint "eagle-import:0207_10")
      (libsource (lib "eagle-import") (part "R-US_0207/10"))
    )
    (comp (ref "U$1")
      (value "DOUBLE")
      (footprint "eagle-import:EDGE-CON4")
      (libsource (lib "eagle-import") (part "DOUBLE"))
    )
    (comp (ref "U$2")
      (value "FLIPCHIP")
      (footprint "eagle-import:FLIPCHIP")
      (libsource (lib "eagle-import") (part "FLIPCHIP"))
    )
    (comp (ref "U$3")
      (value "OUTLINE-DOUBLE")
      (footprint "eagle-import:DOUBLE")
      (libsource (lib "eagle-import") (part "OUTLINE-DOUBLE"))
    )
  )
  (nets
    (net (code "1") (name "+10V") (class "Default")
      (node (ref "R16") (pin "2") (pinfunction "2_2") (pintype "passive"))
      (node (ref "R21") (pin "2") (pinfunction "2_2") (pintype "passive"))
      (node (ref "R26") (pin "2") (pinfunction "2_2") (pintype "passive"))
      (node (ref "R29") (pin "2") (pinfunction "2_2") (pintype "passive"))
      (node (ref "R33") (pin "1") (pinfunction "1_1") (pintype "passive"))
      (node (ref "R36") (pin "2") (pinfunction "2_2") (pintype "passive"))
      (node (ref "R39") (pin "2") (pinfunction "2_2") (pintype "passive"))
      (node (ref "R46") (pin "2") (pinfunction "2_2") (pintype "passive"))
      (node (ref "R51") (pin "2") (pinfunction "2_2") (pintype "passive"))
      (node (ref "R9") (pin "2") (pinfunction "2_2") (pintype "passive"))
      (node (ref "U$1") (pin "AA2") (pinfunction "1_AA2") (pintype "bidirectional"))
    )
    (net (code "2") (name "-15V") (class "Default")
      (node (ref "R1") (pin "1") (pinfunction "1_1") (pintype "passive"))
      (node (ref "R10") (pin "1") (pinfunction "1_1") (pintype "passive"))
      (node (ref "R11") (pin "1") (pinfunction "1_1") (pintype "passive"))
      (node (ref "R12") (pin "1") (pinfunction "1_1") (pintype "passive"))
      (node (ref "R13") (pin "1") (pinfunction "1_1") (pintype "passive"))
      (node (ref "R14") (pin "1") (pinfunction "1_1") (pintype "passive"))
      (node (ref "R15") (pin "1") (pinfunction "1_1") (pintype "passive"))
      (node (ref "R17") (pin "1") (pinfunction "1_1") (pintype "passive"))
      (node (ref "R18") (pin "1") (pinfunction "1_1") (pintype "passive"))
      (node (ref "R19") (pin "1") (pinfunction "1_1") (pintype "passive"))
      (node (ref "R2") (pin "1") (pinfunction "1_1") (pintype "passive"))
      (node (ref "R20") (pin "1") (pinfunction "1_1") (pintype "passive"))
      (node (ref "R22") (pin "1") (pinfunction "1_1") (pintype "passive"))
      (node (ref "R23") (pin "1") (pinfunction "1_1") (pintype "passive"))
      (node (ref "R24") (pin "1") (pinfunction "1_1") (pintype "passive"))
      (node (ref "R25") (pin "1") (pinfunction "1_1") (pintype "passive"))
      (node (ref "R28") (pin "1") (pinfunction "1_1") (pintype "passive"))
      (node (ref "R3") (pin "1") (pinfunction "1_1") (pintype "passive"))
      (node (ref "R30") (pin "1") (pinfunction "1_1") (pintype "passive"))
      (node (ref "R31") (pin "1") (pinfunction "1_1") (pintype "passive"))
      (node (ref "R34") (pin "1") (pinfunction "1_1") (pintype "passive"))
      (node (ref "R35") (pin "1") (pinfunction "1_1") (pintype "passive"))
      (node (ref "R37") (pin "1") (pinfunction "1_1") (pintype "passive"))
      (node (ref "R38") (pin "1") (pinfunction "1_1") (pintype "passive"))
      (node (ref "R4") (pin "1") (pinfunction "1_1") (pintype "passive"))
      (node (ref "R40") (pin "1") (pinfunction "1_1") (pintype "passive"))
      (node (ref "R41") (pin "1") (pinfunction "1_1") (pintype "passive"))
      (node (ref "R42") (pin "2") (pinfunction "2_2") (pintype "passive"))
      (node (ref "R43") (pin "1") (pinfunction "1_1") (pintype "passive"))
      (node (ref "R44") (pin "1") (pinfunction "1_1") (pintype "passive"))
      (node (ref "R45") (pin "1") (pinfunction "1_1") (pintype "passive"))
      (node (ref "R47") (pin "1") (pinfunction "1_1") (pintype "passive"))
      (node (ref "R48") (pin "1") (pinfunction "1_1") (pintype "passive"))
      (node (ref "R49") (pin "1") (pinfunction "1_1") (pintype "passive"))
      (node (ref "R5") (pin "1") (pinfunction "1_1") (pintype "passive"))
      (node (ref "R50") (pin "1") (pinfunction "1_1") (pintype "passive"))
      (node (ref "R52") (pin "1") (pinfunction "1_1") (pintype "passive"))
      (node (ref "R53") (pin "1") (pinfunction "1_1") (pintype "passive"))
      (node (ref "R54") (pin "1") (pinfunction "1_1") (pintype "passive"))
      (node (ref "R55") (pin "1") (pinfunction "1_1") (pintype "passive"))
      (node (ref "R56") (pin "1") (pinfunction "1_1") (pintype "passive"))
      (node (ref "R57") (pin "1") (pinfunction "1_1") (pintype "passive"))
      (node (ref "R58") (pin "1") (pinfunction "1_1") (pintype "passive"))
      (node (ref "R59") (pin "1") (pinfunction "1_1") (pintype "passive"))
      (node (ref "R6") (pin "1") (pinfunction "1_1") (pintype "passive"))
      (node (ref "R60") (pin "1") (pinfunction "1_1") (pintype "passive"))
      (node (ref "R61") (pin "1") (pinfunction "1_1") (pintype "passive"))
      (node (ref "R62") (pin "1") (pinfunction "1_1") (pintype "passive"))
      (node (ref "R63") (pin "1") (pinfunction "1_1") (pintype "passive"))
      (node (ref "R64") (pin "1") (pinfunction "1_1") (pintype "passive"))
      (node (ref "R65") (pin "1") (pinfunction "1_1") (pintype "passive"))
      (node (ref "R7") (pin "1") (pinfunction "1_1") (pintype "passive"))
      (node (ref "R8") (pin "1") (pinfunction "1_1") (pintype "passive"))
      (node (ref "U$1") (pin "AB2") (pinfunction "1_AB2") (pintype "bidirectional"))
    )
    (net (code "3") (name "/-0.7V") (class "Default")
      (node (ref "D10") (pin "C") (pinfunction "C_C") (pintype "passive"))
      (node (ref "D102") (pin "A") (pinfunction "A_A") (pintype "passive"))
      (node (ref "D103") (pin "C") (pinfunction "C_C") (pintype "passive"))
      (node (ref "D107") (pin "C") (pinfunction "C_C") (pintype "passive"))
      (node (ref "D110") (pin "C") (pinfunction "C_C") (pintype "passive"))
      (node (ref "D112") (pin "C") (pinfunction "C_C") (pintype "passive"))
      (node (ref "D115") (pin "C") (pinfunction "C_C") (pintype "passive"))
      (node (ref "D117") (pin "C") (pinfunction "C_C") (pintype "passive"))
      (node (ref "D121") (pin "C") (pinfunction "C_C") (pintype "passive"))
      (node (ref "D14") (pin "C") (pinfunction "C_C") (pintype "passive"))
      (node (ref "D15") (pin "C") (pinfunction "C_C") (pintype "passive"))
      (node (ref "D21") (pin "C") (pinfunction "C_C") (pintype "passive"))
      (node (ref "D22") (pin "C") (pinfunction "C_C") (pintype "passive"))
      (node (ref "D29") (pin "C") (pinfunction "C_C") (pintype "passive"))
      (node (ref "D3") (pin "C") (pinfunction "C_C") (pintype "passive"))
      (node (ref "D36") (pin "C") (pinfunction "C_C") (pintype "passive"))
      (node (ref "D37") (pin "C") (pinfunction "C_C") (pintype "passive"))
      (node (ref "D4") (pin "C") (pinfunction "C_C") (pintype "passive"))
      (node (ref "D61") (pin "C") (pinfunction "C_C") (pintype "passive"))
      (node (ref "D86") (pin "C") (pinfunction "C_C") (pintype "passive"))
      (node (ref "D87") (pin "C") (pinfunction "C_C") (pintype "passive"))
      (node (ref "D9") (pin "C") (pinfunction "C_C") (pintype "passive"))
      (node (ref "D94") (pin "C") (pinfunction "C_C") (pintype "passive"))
      (node (ref "D95") (pin "C") (pinfunction "C_C") (pintype "passive"))
      (node (ref "D99") (pin "C") (pinfunction "C_C") (pintype "passive"))
    )
    (net (code "4") (name "/-3V") (class "Default")
      (node (ref "C17") (pin "2") (pinfunction "2_2") (pintype "passive"))
      (node (ref "D100") (pin "C") (pinfunction "C_C") (pintype "passive"))
      (node (ref "D124") (pin "A") (pinfunction "A_A") (pintype "passive"))
      (node (ref "D27") (pin "A") (pinfunction "A_A") (pintype "passive"))
      (node (ref "D53") (pin "A") (pinfunction "A_A") (pintype "passive"))
      (node (ref "D58") (pin "A") (pinfunction "A_A") (pintype "passive"))
      (node (ref "D59") (pin "A") (pinfunction "A_A") (pintype "passive"))
      (node (ref "D64") (pin "A") (pinfunction "A_A") (pintype "passive"))
      (node (ref "D73") (pin "A") (pinfunction "A_A") (pintype "passive"))
      (node (ref "D84") (pin "A") (pinfunction "A_A") (pintype "passive"))
      (node (ref "R56") (pin "2") (pinfunction "2_2") (pintype "passive"))
    )
    (net (code "5") (name "/A-D_CONV") (class "Default")
      (node (ref "D120") (pin "A") (pinfunction "A_A") (pintype "passive"))
      (node (ref "D2") (pin "A") (pinfunction "A_A") (pintype "passive"))
      (node (ref "D3") (pin "A") (pinfunction "A_A") (pintype "passive"))
      (node (ref "U$1") (pin "BP2") (pinfunction "1_BP2") (pintype "bidirectional"))
    )
    (net (code "6") (name "/AC0+1") (class "Default")
      (node (ref "D36") (pin "A") (pinfunction "A_A") (pintype "passive"))
      (node (ref "D39") (pin "A") (pinfunction "A_A") (pintype "passive"))
      (node (ref "U$1") (pin "AT2") (pinfunction "1_AT2") (pintype "bidirectional"))
    )
    (net (code "7") (name "/AC0+2") (class "Default")
      (node (ref "D22") (pin "A") (pinfunction "A_A") (pintype "passive"))
      (node (ref "D26") (pin "A") (pinfunction "A_A") (pintype "passive"))
      (node (ref "U$1") (pin "BD2") (pinfunction "1_BD2") (pintype "bidirectional"))
    )
    (net (code "8") (name "/AC0-1") (class "Default")
      (node (ref "D29") (pin "A") (pinfunction "A_A") (pintype "passive"))
      (node (ref "D31") (pin "A") (pinfunction "A_A") (pintype "passive"))
      (node (ref "U$1") (pin "BA2") (pinfunction "1_BA2") (pintype "bidirectional"))
    )
    (net (code "9") (name "/AC0-2") (class "Default")
      (node (ref "D15") (pin "A") (pinfunction "A_A") (pintype "passive"))
      (node (ref "D17") (pin "A") (pinfunction "A_A") (pintype "passive"))
      (node (ref "U$1") (pin "BF2") (pinfunction "1_BF2") (pintype "bidirectional"))
    )
    (net (code "10") (name "/AC1+1") (class "Default")
      (node (ref "D87") (pin "A") (pinfunction "A_A") (pintype "passive"))
      (node (ref "D89") (pin "A") (pinfunction "A_A") (pintype "passive"))
      (node (ref "U$1") (pin "AU2") (pinfunction "1_AU2") (pintype "bidirectional"))
    )
    (net (code "11") (name "/AC1+2") (class "Default")
      (node (ref "D105") (pin "A") (pinfunction "A_A") (pintype "passive"))
      (node (ref "D99") (pin "A") (pinfunction "A_A") (pintype "passive"))
      (node (ref "U$1") (pin "BE2") (pinfunction "1_BE2") (pintype "bidirectional"))
    )
    (net (code "12") (name "/AC1-1") (class "Default")
      (node (ref "D95") (pin "A") (pinfunction "A_A") (pintype "passive"))
      (node (ref "D97") (pin "A") (pinfunction "A_A") (pintype "passive"))
      (node (ref "U$1") (pin "BB2") (pinfunction "1_BB2") (pintype "bidirectional"))
    )
    (net (code "13") (name "/AC1-2") (class "Default")
      (node (ref "D107") (pin "A") (pinfunction "A_A") (pintype "passive"))
      (node (ref "D109") (pin "A") (pinfunction "A_A") (pintype "passive"))
      (node (ref "U$1") (pin "BH2") (pinfunction "1_BH2") (pintype "bidirectional"))
    )
    (net (code "14") (name "/ADD_ENABLE") (class "Default")
      (node (ref "D43") (pin "A") (pinfunction "A_A") (pintype "passive"))
      (node (ref "U$1") (pin "AL2") (pinfunction "1_AL2") (pintype "bidirectional"))
    )
    (net (code "15") (name "/CARRY_IN") (class "Default")
      (node (ref "C11") (pin "2") (pinfunction "2_2") (pintype "passive"))
      (node (ref "D61") (pin "A") (pinfunction "A_A") (pintype "passive"))
      (node (ref "R32") (pin "2") (pinfunction "2_2") (pintype "passive"))
      (node (ref "R66") (pin "2") (pinfunction "2_2") (pintype "passive"))
      (node (ref "U$1") (pin "AH2") (pinfunction "1_AH2") (pintype "bidirectional"))
    )
    (net (code "16") (name "/CARRY_OUT") (class "Default")
      (node (ref "D53") (pin "C") (pinfunction "C_C") (pintype "passive"))
      (node (ref "Q4") (pin "3") (pinfunction "C_3") (pintype "passive"))
      (node (ref "Q5") (pin "3") (pinfunction "C_3") (pintype "passive"))
      (node (ref "R24") (pin "2") (pinfunction "2_2") (pintype "passive"))
      (node (ref "U$1") (pin "AJ2") (pinfunction "1_AJ2") (pintype "bidirectional"))
    )
    (net (code "17") (name "/CARRY_PULSE") (class "Default")
      (node (ref "D37") (pin "A") (pinfunction "A_A") (pintype "passive"))
      (node (ref "D40") (pin "A") (pinfunction "A_A") (pintype "passive"))
      (node (ref "D76") (pin "A") (pinfunction "A_A") (pintype "passive"))
      (node (ref "U$1") (pin "AD2") (pinfunction "1_AD2") (pintype "bidirectional"))
    )
    (net (code "18") (name "/CLEAR") (class "Default")
      (node (ref "D55") (pin "A") (pinfunction "A_A") (pintype "passive"))
      (node (ref "U$1") (pin "AR2") (pinfunction "1_AR2") (pintype "bidirectional"))
    )
    (net (code "19") (name "/COMP") (class "Default")
      (node (ref "D32") (pin "A") (pinfunction "A_A") (pintype "passive"))
      (node (ref "U$1") (pin "AM2") (pinfunction "1_AM2") (pintype "bidirectional"))
    )
    (net (code "20") (name "/COMPARITOR") (class "Default")
      (node (ref "D4") (pin "A") (pinfunction "A_A") (pintype "passive"))
      (node (ref "D7") (pin "A") (pinfunction "A_A") (pintype "passive"))
      (node (ref "U$1") (pin "BV2") (pinfunction "1_BV2") (pintype "bidirectional"))
    )
    (net (code "21") (name "/HALF_ADD") (class "Default")
      (node (ref "D18") (pin "A") (pinfunction "A_A") (pintype "passive"))
      (node (ref "U$1") (pin "AN2") (pinfunction "1_AN2") (pintype "bidirectional"))
    )
    (net (code "22") (name "/INPUT_MIXER") (class "Default")
      (node (ref "D73") (pin "C") (pinfunction "C_C") (pintype "passive"))
      (node (ref "D74") (pin "A") (pinfunction "A_A") (pintype "passive"))
      (node (ref "R42") (pin "1") (pinfunction "1_1") (pintype "passive"))
      (node (ref "U$1") (pin "AE2") (pinfunction "1_AE2") (pintype "bidirectional"))
    )
    (net (code "23") (name "/MB1") (class "Default")
      (node (ref "D1") (pin "A") (pinfunction "A_A") (pintype "passive"))
      (node (ref "D10") (pin "A") (pinfunction "A_A") (pintype "passive"))
      (node (ref "D12") (pin "A") (pinfunction "A_A") (pintype "passive"))
      (node (ref "D19") (pin "A") (pinfunction "A_A") (pintype "passive"))
      (node (ref "D42") (pin "A") (pinfunction "A_A") (pintype "passive"))
      (node (ref "U$1") (pin "AK2") (pinfunction "1_AK2") (pintype "bidirectional"))
    )
    (net (code "24") (name "/MB1-1") (class "Default")
      (node (ref "D121") (pin "A") (pinfunction "A_A") (pintype "passive"))
      (node (ref "D123") (pin "A") (pinfunction "A_A") (pintype "passive"))
      (node (ref "U$1") (pin "BU2") (pinfunction "1_BU2") (pintype "bidirectional"))
    )
    (net (code "25") (name "/MB_2_AC") (class "Default")
      (node (ref "D8") (pin "A") (pinfunction "A_A") (pintype "passive"))
      (node (ref "D9") (pin "A") (pinfunction "A_A") (pintype "passive"))
      (node (ref "U$1") (pin "BR2") (pinfunction "1_BR2") (pintype "bidirectional"))
    )
    (net (code "26") (name "/ONE") (class "Default")
      (node (ref "D84") (pin "C") (pinfunction "C_C") (pintype "passive"))
      (node (ref "Q11") (pin "3") (pinfunction "C_3") (pintype "passive"))
      (node (ref "R48") (pin "2") (pinfunction "2_2") (pintype "passive"))
      (node (ref "U$1") (pin "AP2") (pinfunction "1_AP2") (pintype "bidirectional"))
    )
    (net (code "27") (name "/RAL") (class "Default")
      (node (ref "D35") (pin "A") (pinfunction "A_A") (pintype "passive"))
      (node (ref "D85") (pin "A") (pinfunction "A_A") (pintype "passive"))
      (node (ref "D86") (pin "A") (pinfunction "A_A") (pintype "passive"))
      (node (ref "U$1") (pin "AV2") (pinfunction "1_AV2") (pintype "bidirectional"))
    )
    (net (code "28") (name "/RAR") (class "Default")
      (node (ref "D28") (pin "A") (pinfunction "A_A") (pintype "passive"))
      (node (ref "D93") (pin "A") (pinfunction "A_A") (pintype "passive"))
      (node (ref "D94") (pin "A") (pinfunction "A_A") (pintype "passive"))
      (node (ref "U$1") (pin "BJ2") (pinfunction "1_BJ2") (pintype "bidirectional"))
    )
    (net (code "29") (name "/RTL") (class "Default")
      (node (ref "D20") (pin "A") (pinfunction "A_A") (pintype "passive"))
      (node (ref "D21") (pin "A") (pinfunction "A_A") (pintype "passive"))
      (node (ref "D98") (pin "A") (pinfunction "A_A") (pintype "passive"))
      (node (ref "U$1") (pin "BK2") (pinfunction "1_BK2") (pintype "bidirectional"))
    )
    (net (code "30") (name "/RTR") (class "Default")
      (node (ref "D106") (pin "A") (pinfunction "A_A") (pintype "passive"))
      (node (ref "D13") (pin "A") (pinfunction "A_A") (pintype "passive"))
      (node (ref "D14") (pin "A") (pinfunction "A_A") (pintype "passive"))
      (node (ref "U$1") (pin "BL2") (pinfunction "1_BL2") (pintype "bidirectional"))
    )
    (net (code "31") (name "/SET") (class "Default")
      (node (ref "D71") (pin "A") (pinfunction "A_A") (pintype "passive"))
      (node (ref "U$1") (pin "AS2") (pinfunction "1_AS2") (pintype "bidirectional"))
    )
    (net (code "32") (name "/SR") (class "Default")
      (node (ref "C21") (pin "1") (pinfunction "1_1") (pintype "passive"))
      (node (ref "D112") (pin "A") (pinfunction "A_A") (pintype "passive"))
      (node (ref "D114") (pin "A") (pinfunction "A_A") (pintype "passive"))
      (node (ref "U$1") (pin "BS2") (pinfunction "1_BS2") (pintype "bidirectional"))
    )
    (net (code "33") (name "/SR_2_AC") (class "Default")
      (node (ref "D110") (pin "A") (pinfunction "A_A") (pintype "passive"))
      (node (ref "D111") (pin "A") (pinfunction "A_A") (pintype "passive"))
      (node (ref "U$1") (pin "BN2") (pinfunction "1_BN2") (pintype "bidirectional"))
    )
    (net (code "34") (name "/TTI") (class "Default")
      (node (ref "D117") (pin "A") (pinfunction "A_A") (pintype "passive"))
      (node (ref "D119") (pin "A") (pinfunction "A_A") (pintype "passive"))
      (node (ref "U$1") (pin "BT2") (pinfunction "1_BT2") (pintype "bidirectional"))
    )
    (net (code "35") (name "/TTI_2_AC") (class "Default")
      (node (ref "D115") (pin "A") (pinfunction "A_A") (pintype "passive"))
      (node (ref "D116") (pin "A") (pinfunction "A_A") (pintype "passive"))
      (node (ref "U$1") (pin "BM2") (pinfunction "1_BM2") (pintype "bidirectional"))
    )
    (net (code "36") (name "/ZERO") (class "Default")
      (node (ref "D124") (pin "C") (pinfunction "C_C") (pintype "passive"))
      (node (ref "Q12") (pin "3") (pinfunction "C_3") (pintype "passive"))
      (node (ref "R54") (pin "2") (pinfunction "2_2") (pintype "passive"))
      (node (ref "U$1") (pin "AF2") (pinfunction "1_AF2") (pintype "bidirectional"))
    )
    (net (code "37") (name "GND") (class "Default")
      (node (ref "C17") (pin "1") (pinfunction "1_1") (pintype "passive"))
      (node (ref "C21") (pin "2") (pinfunction "2_2") (pintype "passive"))
      (node (ref "D103") (pin "A") (pinfunction "A_A") (pintype "passive"))
      (node (ref "D51") (pin "A") (pinfunction "A_A") (pintype "passive"))
      (node (ref "D82") (pin "A") (pinfunction "A_A") (pintype "passive"))
      (node (ref "Q1") (pin "1") (pinfunction "E_1") (pintype "passive"))
      (node (ref "Q10") (pin "1") (pinfunction "E_1") (pintype "passive"))
      (node (ref "Q11") (pin "1") (pinfunction "E_1") (pintype "passive"))
      (node (ref "Q12") (pin "1") (pinfunction "E_1") (pintype "passive"))
      (node (ref "Q2") (pin "1") (pinfunction "E_1") (pintype "passive"))
      (node (ref "Q4") (pin "1") (pinfunction "E_1") (pintype "passive"))
      (node (ref "Q6") (pin "1") (pinfunction "E_1") (pintype "passive"))
      (node (ref "Q7") (pin "1") (pinfunction "E_1") (pintype "passive"))
      (node (ref "Q8") (pin "1") (pinfunction "E_1") (pintype "passive"))
      (node (ref "U$1") (pin "AC2") (pinfunction "1_AC2") (pintype "bidirectional"))
      (node (ref "U$1") (pin "BC2") (pinfunction "1_BC2") (pintype "bidirectional"))
    )
    (net (code "38") (name "Net-(C1-Pad1)") (class "Default")
      (node (ref "C1") (pin "1") (pinfunction "1_1") (pintype "passive"))
      (node (ref "D1") (pin "C") (pinfunction "C_C") (pintype "passive"))
      (node (ref "D2") (pin "C") (pinfunction "C_C") (pintype "passive"))
      (node (ref "D5") (pin "A") (pinfunction "A_A") (pintype "passive"))
      (node (ref "R1") (pin "2") (pinfunction "2_2") (pintype "passive"))
    )
    (net (code "39") (name "Net-(C1-Pad2)") (class "Default")
      (node (ref "C1") (pin "2") (pinfunction "2_2") (pintype "passive"))
      (node (ref "D5") (pin "C") (pinfunction "C_C") (pintype "passive"))
      (node (ref "D6") (pin "A") (pinfunction "A_A") (pintype "passive"))
      (node (ref "D7") (pin "C") (pinfunction "C_C") (pintype "passive"))
      (node (ref "R2") (pin "2") (pinfunction "2_2") (pintype "passive"))
    )
    (net (code "40") (name "Net-(C2-Pad1)") (class "Default")
      (node (ref "C2") (pin "1") (pinfunction "1_1") (pintype "passive"))
      (node (ref "D8") (pin "C") (pinfunction "C_C") (pintype "passive"))
      (node (ref "R3") (pin "2") (pinfunction "2_2") (pintype "passive"))
    )
    (net (code "41") (name "Net-(C2-Pad2)") (class "Default")
      (node (ref "C2") (pin "2") (pinfunction "2_2") (pintype "passive"))
      (node (ref "D11") (pin "A") (pinfunction "A_A") (pintype "passive"))
      (node (ref "D12") (pin "C") (pinfunction "C_C") (pintype "passive"))
      (node (ref "R4") (pin "2") (pinfunction "2_2") (pintype "passive"))
    )
    (net (code "42") (name "Net-(C3-Pad1)") (class "Default")
      (node (ref "C3") (pin "1") (pinfunction "1_1") (pintype "passive"))
      (node (ref "D13") (pin "C") (pinfunction "C_C") (pintype "passive"))
      (node (ref "R5") (pin "2") (pinfunction "2_2") (pintype "passive"))
    )
    (net (code "43") (name "Net-(C3-Pad2)") (class "Default")
      (node (ref "C3") (pin "2") (pinfunction "2_2") (pintype "passive"))
      (node (ref "D16") (pin "A") (pinfunction "A_A") (pintype "passive"))
      (node (ref "D17") (pin "C") (pinfunction "C_C") (pintype "passive"))
      (node (ref "R6") (pin "2") (pinfunction "2_2") (pintype "passive"))
    )
    (net (code "44") (name "Net-(C4-Pad1)") (class "Default")
      (node (ref "C4") (pin "1") (pinfunction "1_1") (pintype "passive"))
      (node (ref "D20") (pin "C") (pinfunction "C_C") (pintype "passive"))
      (node (ref "R7") (pin "2") (pinfunction "2_2") (pintype "passive"))
    )
    (net (code "45") (name "Net-(C4-Pad2)") (class "Default")
      (node (ref "C4") (pin "2") (pinfunction "2_2") (pintype "passive"))
      (node (ref "D25") (pin "A") (pinfunction "A_A") (pintype "passive"))
      (node (ref "D26") (pin "C") (pinfunction "C_C") (pintype "passive"))
      (node (ref "R10") (pin "2") (pinfunction "2_2") (pintype "passive"))
    )
    (net (code "46") (name "Net-(C5-Pad1)") (class "Default")
      (node (ref "C5") (pin "1") (pinfunction "1_1") (pintype "passive"))
      (node (ref "D28") (pin "C") (pinfunction "C_C") (pintype "passive"))
      (node (ref "R12") (pin "2") (pinfunction "2_2") (pintype "passive"))
    )
    (net (code "47") (name "Net-(C5-Pad2)") (class "Default")
      (node (ref "C5") (pin "2") (pinfunction "2_2") (pintype "passive"))
      (node (ref "D30") (pin "A") (pinfunction "A_A") (pintype "passive"))
      (node (ref "D31") (pin "C") (pinfunction "C_C") (pintype "passive"))
      (node (ref "R13") (pin "2") (pinfunction "2_2") (pintype "passive"))
    )
    (net (code "48") (name "Net-(C6-Pad1)") (class "Default")
      (node (ref "C6") (pin "1") (pinfunction "1_1") (pintype "passive"))
      (node (ref "D35") (pin "C") (pinfunction "C_C") (pintype "passive"))
      (node (ref "R14") (pin "2") (pinfunction "2_2") (pintype "passive"))
    )
    (net (code "49") (name "Net-(C6-Pad2)") (class "Default")
      (node (ref "C6") (pin "2") (pinfunction "2_2") (pintype "passive"))
      (node (ref "D38") (pin "A") (pinfunction "A_A") (pintype "passive"))
      (node (ref "D39") (pin "C") (pinfunction "C_C") (pintype "passive"))
      (node (ref "R17") (pin "2") (pinfunction "2_2") (pintype "passive"))
    )
    (net (code "50") (name "Net-(C7-Pad1)") (class "Default")
      (node (ref "C7") (pin "1") (pinfunction "1_1") (pintype "passive"))
      (node (ref "D44") (pin "C") (pinfunction "C_C") (pintype "passive"))
      (node (ref "D45") (pin "C") (pinfunction "C_C") (pintype "passive"))
      (node (ref "R18") (pin "2") (pinfunction "2_2") (pintype "passive"))
    )
    (net (code "51") (name "Net-(C7-Pad2)") (class "Default")
      (node (ref "C7") (pin "2") (pinfunction "2_2") (pintype "passive"))
      (node (ref "D50") (pin "A") (pinfunction "A_A") (pintype "passive"))
      (node (ref "D51") (pin "C") (pinfunction "C_C") (pintype "passive"))
      (node (ref "R22") (pin "2") (pinfunction "2_2") (pintype "passive"))
    )
    (net (code "52") (name "Net-(C8-Pad1)") (class "Default")
      (node (ref "C8") (pin "1") (pinfunction "1_1") (pintype "passive"))
      (node (ref "D40") (pin "C") (pinfunction "C_C") (pintype "passive"))
      (node (ref "D41") (pin "C") (pinfunction "C_C") (pintype "passive"))
      (node (ref "D48") (pin "A") (pinfunction "A_A") (pintype "passive"))
      (node (ref "R19") (pin "2") (pinfunction "2_2") (pintype "passive"))
    )
    (net (code "53") (name "Net-(C12-Pad2)") (class "Default")
      (node (ref "C12") (pin "2") (pinfunction "2_2") (pintype "passive"))
      (node (ref "D70") (pin "A") (pinfunction "A_A") (pintype "passive"))
      (node (ref "D76") (pin "C") (pinfunction "C_C") (pintype "passive"))
      (node (ref "D77") (pin "C") (pinfunction "C_C") (pintype "passive"))
      (node (ref "R40") (pin "2") (pinfunction "2_2") (pintype "passive"))
    )
    (net (code "54") (name "Net-(C14-Pad1)") (class "Default")
      (node (ref "C14") (pin "1") (pinfunction "1_1") (pintype "passive"))
      (node (ref "D72") (pin "C") (pinfunction "C_C") (pintype "passive"))
      (node (ref "D78") (pin "C") (pinfunction "C_C") (pintype "passive"))
      (node (ref "R43") (pin "2") (pinfunction "2_2") (pintype "passive"))
    )
    (net (code "55") (name "Net-(C14-Pad2)") (class "Default")
      (node (ref "C14") (pin "2") (pinfunction "2_2") (pintype "passive"))
      (node (ref "D82") (pin "C") (pinfunction "C_C") (pintype "passive"))
      (node (ref "D83") (pin "A") (pinfunction "A_A") (pintype "passive"))
      (node (ref "R44") (pin "2") (pinfunction "2_2") (pintype "passive"))
    )
    (net (code "56") (name "Net-(C15-Pad1)") (class "Default")
      (node (ref "C15") (pin "1") (pinfunction "1_1") (pintype "passive"))
      (node (ref "D85") (pin "C") (pinfunction "C_C") (pintype "passive"))
      (node (ref "R47") (pin "2") (pinfunction "2_2") (pintype "passive"))
    )
    (net (code "57") (name "Net-(C15-Pad2)") (class "Default")
      (node (ref "C15") (pin "2") (pinfunction "2_2") (pintype "passive"))
      (node (ref "D88") (pin "A") (pinfunction "A_A") (pintype "passive"))
      (node (ref "D89") (pin "C") (pinfunction "C_C") (pintype "passive"))
      (node (ref "R49") (pin "2") (pinfunction "2_2") (pintype "passive"))
    )
    (net (code "58") (name "Net-(C16-Pad1)") (class "Default")
      (node (ref "C16") (pin "1") (pinfunction "1_1") (pintype "passive"))
      (node (ref "D93") (pin "C") (pinfunction "C_C") (pintype "passive"))
      (node (ref "R52") (pin "2") (pinfunction "2_2") (pintype "passive"))
    )
    (net (code "59") (name "Net-(C16-Pad2)") (class "Default")
      (node (ref "C16") (pin "2") (pinfunction "2_2") (pintype "passive"))
      (node (ref "D96") (pin "A") (pinfunction "A_A") (pintype "passive"))
      (node (ref "D97") (pin "C") (pinfunction "C_C") (pintype "passive"))
      (node (ref "R53") (pin "2") (pinfunction "2_2") (pintype "passive"))
    )
    (net (code "60") (name "Net-(C18-Pad1)") (class "Default")
      (node (ref "C18") (pin "1") (pinfunction "1_1") (pintype "passive"))
      (node (ref "D98") (pin "C") (pinfunction "C_C") (pintype "passive"))
      (node (ref "R55") (pin "2") (pinfunction "2_2") (pintype "passive"))
    )
    (net (code "61") (name "Net-(C18-Pad2)") (class "Default")
      (node (ref "C18") (pin "2") (pinfunction "2_2") (pintype "passive"))
      (node (ref "D104") (pin "A") (pinfunction "A_A") (pintype "passive"))
      (node (ref "D105") (pin "C") (pinfunction "C_C") (pintype "passive"))
      (node (ref "R57") (pin "2") (pinfunction "2_2") (pintype "passive"))
    )
    (net (code "62") (name "Net-(C19-Pad1)") (class "Default")
      (node (ref "C19") (pin "1") (pinfunction "1_1") (pintype "passive"))
      (node (ref "D106") (pin "C") (pinfunction "C_C") (pintype "passive"))
      (node (ref "R58") (pin "2") (pinfunction "2_2") (pintype "passive"))
    )
    (net (code "63") (name "Net-(C19-Pad2)") (class "Default")
      (node (ref "C19") (pin "2") (pinfunction "2_2") (pintype "passive"))
      (node (ref "D108") (pin "A") (pinfunction "A_A") (pintype "passive"))
      (node (ref "D109") (pin "C") (pinfunction "C_C") (pintype "passive"))
      (node (ref "R59") (pin "2") (pinfunction "2_2") (pintype "passive"))
    )
    (net (code "64") (name "Net-(C20-Pad1)") (class "Default")
      (node (ref "C20") (pin "1") (pinfunction "1_1") (pintype "passive"))
      (node (ref "D111") (pin "C") (pinfunction "C_C") (pintype "passive"))
      (node (ref "R60") (pin "2") (pinfunction "2_2") (pintype "passive"))
    )
    (net (code "65") (name "Net-(C20-Pad2)") (class "Default")
      (node (ref "C20") (pin "2") (pinfunction "2_2") (pintype "passive"))
      (node (ref "D113") (pin "A") (pinfunction "A_A") (pintype "passive"))
      (node (ref "D114") (pin "C") (pinfunction "C_C") (pintype "passive"))
      (node (ref "R61") (pin "2") (pinfunction "2_2") (pintype "passive"))
    )
    (net (code "66") (name "Net-(C22-Pad1)") (class "Default")
      (node (ref "C22") (pin "1") (pinfunction "1_1") (pintype "passive"))
      (node (ref "D116") (pin "C") (pinfunction "C_C") (pintype "passive"))
      (node (ref "R62") (pin "2") (pinfunction "2_2") (pintype "passive"))
    )
    (net (code "67") (name "Net-(C22-Pad2)") (class "Default")
      (node (ref "C22") (pin "2") (pinfunction "2_2") (pintype "passive"))
      (node (ref "D118") (pin "A") (pinfunction "A_A") (pintype "passive"))
      (node (ref "D119") (pin "C") (pinfunction "C_C") (pintype "passive"))
      (node (ref "R63") (pin "2") (pinfunction "2_2") (pintype "passive"))
    )
    (net (code "68") (name "Net-(C23-Pad1)") (class "Default")
      (node (ref "C23") (pin "1") (pinfunction "1_1") (pintype "passive"))
      (node (ref "D120") (pin "C") (pinfunction "C_C") (pintype "passive"))
      (node (ref "R64") (pin "2") (pinfunction "2_2") (pintype "passive"))
    )
    (net (code "69") (name "Net-(C23-Pad2)") (class "Default")
      (node (ref "C23") (pin "2") (pinfunction "2_2") (pintype "passive"))
      (node (ref "D122") (pin "A") (pinfunction "A_A") (pintype "passive"))
      (node (ref "D123") (pin "C") (pinfunction "C_C") (pintype "passive"))
      (node (ref "R65") (pin "2") (pinfunction "2_2") (pintype "passive"))
    )
    (net (code "70") (name "Net-(D11-PadC)") (class "Default")
      (node (ref "D11") (pin "C") (pinfunction "C_C") (pintype "passive"))
      (node (ref "D16") (pin "C") (pinfunction "C_C") (pintype "passive"))
      (node (ref "D25") (pin "C") (pinfunction "C_C") (pintype "passive"))
      (node (ref "D30") (pin "C") (pinfunction "C_C") (pintype "passive"))
      (node (ref "D38") (pin "C") (pinfunction "C_C") (pintype "passive"))
      (node (ref "D50") (pin "C") (pinfunction "C_C") (pintype "passive"))
      (node (ref "D52") (pin "A") (pinfunction "A_A") (pintype "passive"))
      (node (ref "D6") (pin "C") (pinfunction "C_C") (pintype "passive"))
      (node (ref "R25") (pin "2") (pinfunction "2_2") (pintype "passive"))
    )
    (net (code "71") (name "Net-(D18-PadC)") (class "Default")
      (node (ref "D18") (pin "C") (pinfunction "C_C") (pintype "passive"))
      (node (ref "D19") (pin "C") (pinfunction "C_C") (pintype "passive"))
      (node (ref "D23") (pin "C") (pinfunction "C_C") (pintype "passive"))
      (node (ref "R8") (pin "2") (pinfunction "2_2") (pintype "passive"))
    )
    (net (code "72") (name "Net-(D23-PadA)") (class "Default")
      (node (ref "D23") (pin "A") (pinfunction "A_A") (pintype "passive"))
      (node (ref "D24") (pin "C") (pinfunction "C_C") (pintype "passive"))
    )
    (net (code "73") (name "Net-(D32-PadC)") (class "Default")
      (node (ref "D32") (pin "C") (pinfunction "C_C") (pintype "passive"))
      (node (ref "D33") (pin "C") (pinfunction "C_C") (pintype "passive"))
      (node (ref "R15") (pin "2") (pinfunction "2_2") (pintype "passive"))
    )
    (net (code "74") (name "Net-(D33-PadA)") (class "Default")
      (node (ref "D33") (pin "A") (pinfunction "A_A") (pintype "passive"))
      (node (ref "D34") (pin "C") (pinfunction "C_C") (pintype "passive"))
    )
    (net (code "75") (name "Net-(D42-PadC)") (class "Default")
      (node (ref "D42") (pin "C") (pinfunction "C_C") (pintype "passive"))
      (node (ref "D43") (pin "C") (pinfunction "C_C") (pintype "passive"))
      (node (ref "D46") (pin "C") (pinfunction "C_C") (pintype "passive"))
      (node (ref "D49") (pin "C") (pinfunction "C_C") (pintype "passive"))
      (node (ref "R20") (pin "2") (pinfunction "2_2") (pintype "passive"))
    )
    (net (code "76") (name "Net-(D46-PadA)") (class "Default")
      (node (ref "D46") (pin "A") (pinfunction "A_A") (pintype "passive"))
      (node (ref "D47") (pin "C") (pinfunction "C_C") (pintype "passive"))
    )
    (net (code "77") (name "Net-(D54-PadA)") (class "Default")
      (node (ref "D54") (pin "A") (pinfunction "A_A") (pintype "passive"))
      (node (ref "D62") (pin "A") (pinfunction "A_A") (pintype "passive"))
      (node (ref "R66") (pin "1") (pinfunction "1_1") (pintype "passive"))
    )
    (net (code "78") (name "Net-(D55-PadC)") (class "Default")
      (node (ref "D55") (pin "C") (pinfunction "C_C") (pintype "passive"))
      (node (ref "D56") (pin "C") (pinfunction "C_C") (pintype "passive"))
      (node (ref "D60") (pin "C") (pinfunction "C_C") (pintype "passive"))
      (node (ref "R28") (pin "2") (pinfunction "2_2") (pintype "passive"))
    )
    (net (code "79") (name "Net-(D56-PadA)") (class "Default")
      (node (ref "D56") (pin "A") (pinfunction "A_A") (pintype "passive"))
      (node (ref "D57") (pin "C") (pinfunction "C_C") (pintype "passive"))
    )
    (net (code "80") (name "Net-(D63-PadC)") (class "Default")
      (node (ref "D63") (pin "C") (pinfunction "C_C") (pintype "passive"))
      (node (ref "D66") (pin "C") (pinfunction "C_C") (pintype "passive"))
      (node (ref "R38") (pin "2") (pinfunction "2_2") (pintype "passive"))
    )
    (net (code "81") (name "Net-(D65-PadC)") (class "Default")
      (node (ref "D65") (pin "C") (pinfunction "C_C") (pintype "passive"))
      (node (ref "D68") (pin "C") (pinfunction "C_C") (pintype "passive"))
      (node (ref "D71") (pin "C") (pinfunction "C_C") (pintype "passive"))
      (node (ref "D74") (pin "C") (pinfunction "C_C") (pintype "passive"))
      (node (ref "R35") (pin "2") (pinfunction "2_2") (pintype "passive"))
    )
    (net (code "82") (name "Net-(D66-PadA)") (class "Default")
      (node (ref "D66") (pin "A") (pinfunction "A_A") (pintype "passive"))
      (node (ref "D67") (pin "C") (pinfunction "C_C") (pintype "passive"))
    )
    (net (code "83") (name "Net-(D68-PadA)") (class "Default")
      (node (ref "D68") (pin "A") (pinfunction "A_A") (pintype "passive"))
      (node (ref "D69") (pin "C") (pinfunction "C_C") (pintype "passive"))
    )
    (net (code "84") (name "Net-(D79-PadC)") (class "Default")
      (node (ref "D79") (pin "C") (pinfunction "C_C") (pintype "passive"))
      (node (ref "D80") (pin "C") (pinfunction "C_C") (pintype "passive"))
      (node (ref "R45") (pin "2") (pinfunction "2_2") (pintype "passive"))
    )
    (net (code "85") (name "Net-(D80-PadA)") (class "Default")
      (node (ref "D80") (pin "A") (pinfunction "A_A") (pintype "passive"))
      (node (ref "D81") (pin "C") (pinfunction "C_C") (pintype "passive"))
    )
    (net (code "86") (name "Net-(D90-PadC)") (class "Default")
      (node (ref "D90") (pin "C") (pinfunction "C_C") (pintype "passive"))
      (node (ref "D91") (pin "C") (pinfunction "C_C") (pintype "passive"))
      (node (ref "R50") (pin "2") (pinfunction "2_2") (pintype "passive"))
    )
    (net (code "87") (name "Net-(D91-PadA)") (class "Default")
      (node (ref "D91") (pin "A") (pinfunction "A_A") (pintype "passive"))
      (node (ref "D92") (pin "C") (pinfunction "C_C") (pintype "passive"))
    )
    (net (code "88") (name "Net-(D100-PadA)") (class "Default")
      (node (ref "D100") (pin "A") (pinfunction "A_A") (pintype "passive"))
      (node (ref "D101") (pin "C") (pinfunction "C_C") (pintype "passive"))
    )
    (net (code "89") (name "Net-(D101-PadA)") (class "Default")
      (node (ref "D101") (pin "A") (pinfunction "A_A") (pintype "passive"))
      (node (ref "D102") (pin "C") (pinfunction "C_C") (pintype "passive"))
    )
    (net (code "90") (name "Net-(D104-PadC)") (class "Default")
      (node (ref "D104") (pin "C") (pinfunction "C_C") (pintype "passive"))
      (node (ref "D108") (pin "C") (pinfunction "C_C") (pintype "passive"))
      (node (ref "D113") (pin "C") (pinfunction "C_C") (pintype "passive"))
      (node (ref "D118") (pin "C") (pinfunction "C_C") (pintype "passive"))
      (node (ref "D122") (pin "C") (pinfunction "C_C") (pintype "passive"))
      (node (ref "D75") (pin "A") (pinfunction "A_A") (pintype "passive"))
      (node (ref "D83") (pin "C") (pinfunction "C_C") (pintype "passive"))
      (node (ref "D88") (pin "C") (pinfunction "C_C") (pintype "passive"))
      (node (ref "D96") (pin "C") (pinfunction "C_C") (pintype "passive"))
      (node (ref "R41") (pin "2") (pinfunction "2_2") (pintype "passive"))
    )
    (net (code "91") (name "Net-(Q1-B)") (class "Default")
      (node (ref "D24") (pin "A") (pinfunction "A_A") (pintype "passive"))
      (node (ref "Q1") (pin "2") (pinfunction "B_2") (pintype "passive"))
      (node (ref "R9") (pin "1") (pinfunction "1_1") (pintype "passive"))
    )
    (net (code "92") (name "Net-(Q1-C)") (class "Default")
      (node (ref "D27") (pin "C") (pinfunction "C_C") (pintype "passive"))
      (node (ref "D44") (pin "A") (pinfunction "A_A") (pintype "passive"))
      (node (ref "D78") (pin "A") (pinfunction "A_A") (pintype "passive"))
      (node (ref "Q1") (pin "3") (pinfunction "C_3") (pintype "passive"))
      (node (ref "Q2") (pin "3") (pinfunction "C_3") (pintype "passive"))
      (node (ref "R11") (pin "2") (pinfunction "2_2") (pintype "passive"))
    )
    (net (code "93") (name "Net-(Q2-B)") (class "Default")
      (node (ref "D34") (pin "A") (pinfunction "A_A") (pintype "passive"))
      (node (ref "Q2") (pin "2") (pinfunction "B_2") (pintype "passive"))
      (node (ref "R16") (pin "1") (pinfunction "1_1") (pintype "passive"))
    )
    (net (code "94") (name "Net-(Q3-B)") (class "Default")
      (node (ref "C8") (pin "2") (pinfunction "2_2") (pintype "passive"))
      (node (ref "D48") (pin "C") (pinfunction "C_C") (pintype "passive"))
      (node (ref "D54") (pin "C") (pinfunction "C_C") (pintype "passive"))
      (node (ref "Q3") (pin "2") (pinfunction "B_2") (pintype "passive"))
      (node (ref "R23") (pin "2") (pinfunction "2_2") (pintype "passive"))
    )
    (net (code "95") (name "Net-(Q3-C)") (class "Default")
      (node (ref "Q3") (pin "3") (pinfunction "C_3") (pintype "passive"))
      (node (ref "R26") (pin "1") (pinfunction "1_1") (pintype "passive"))
    )
    (net (code "96") (name "Net-(Q3-E)") (class "Default")
      (node (ref "C10") (pin "1") (pinfunction "1_1") (pintype "passive"))
      (node (ref "D52") (pin "C") (pinfunction "C_C") (pintype "passive"))
      (node (ref "D57") (pin "A") (pinfunction "A_A") (pintype "passive"))
      (node (ref "Q3") (pin "1") (pinfunction "E_1") (pintype "passive"))
      (node (ref "Q7") (pin "2") (pinfunction "B_2") (pintype "passive"))
      (node (ref "R29") (pin "1") (pinfunction "1_1") (pintype "passive"))
    )
    (net (code "97") (name "Net-(Q4-B)") (class "Default")
      (node (ref "D47") (pin "A") (pinfunction "A_A") (pintype "passive"))
      (node (ref "Q4") (pin "2") (pinfunction "B_2") (pintype "passive"))
      (node (ref "R21") (pin "1") (pinfunction "1_1") (pintype "passive"))
    )
    (net (code "98") (name "Net-(Q5-B)") (class "Default")
      (node (ref "C9") (pin "1") (pinfunction "1_1") (pintype "passive"))
      (node (ref "Q5") (pin "2") (pinfunction "B_2") (pintype "passive"))
      (node (ref "R27") (pin "1") (pinfunction "1_1") (pintype "passive"))
    )
    (net (code "99") (name "Net-(Q6-B)") (class "Default")
      (node (ref "C11") (pin "1") (pinfunction "1_1") (pintype "passive"))
      (node (ref "Q6") (pin "2") (pinfunction "B_2") (pintype "passive"))
      (node (ref "R32") (pin "1") (pinfunction "1_1") (pintype "passive"))
    )
    (net (code "100") (name "Net-(Q6-C)") (class "Default")
      (node (ref "C9") (pin "2") (pinfunction "2_2") (pintype "passive"))
      (node (ref "D58") (pin "C") (pinfunction "C_C") (pintype "passive"))
      (node (ref "Q6") (pin "3") (pinfunction "C_3") (pintype "passive"))
      (node (ref "R27") (pin "2") (pinfunction "2_2") (pintype "passive"))
      (node (ref "R30") (pin "2") (pinfunction "2_2") (pintype "passive"))
    )
    (net (code "101") (name "Net-(Q7-C)") (class "Default")
      (node (ref "C13") (pin "2") (pinfunction "2_2") (pintype "passive"))
      (node (ref "D49") (pin "A") (pinfunction "A_A") (pintype "passive"))
      (node (ref "D64") (pin "C") (pinfunction "C_C") (pintype "passive"))
      (node (ref "D65") (pin "A") (pinfunction "A_A") (pintype "passive"))
      (node (ref "D72") (pin "A") (pinfunction "A_A") (pintype "passive"))
      (node (ref "D77") (pin "A") (pinfunction "A_A") (pintype "passive"))
      (node (ref "D79") (pin "A") (pinfunction "A_A") (pintype "passive"))
      (node (ref "Q7") (pin "3") (pinfunction "C_3") (pintype "passive"))
      (node (ref "R34") (pin "2") (pinfunction "2_2") (pintype "passive"))
    )
    (net (code "102") (name "Net-(Q8-B)") (class "Default")
      (node (ref "C13") (pin "1") (pinfunction "1_1") (pintype "passive"))
      (node (ref "D69") (pin "A") (pinfunction "A_A") (pintype "passive"))
      (node (ref "D75") (pin "C") (pinfunction "C_C") (pintype "passive"))
      (node (ref "Q8") (pin "2") (pinfunction "B_2") (pintype "passive"))
      (node (ref "Q9") (pin "1") (pinfunction "E_1") (pintype "passive"))
      (node (ref "R36") (pin "1") (pinfunction "1_1") (pintype "passive"))
    )
    (net (code "103") (name "Net-(Q8-C)") (class "Default")
      (node (ref "C10") (pin "2") (pinfunction "2_2") (pintype "passive"))
      (node (ref "D41") (pin "A") (pinfunction "A_A") (pintype "passive"))
      (node (ref "D45") (pin "A") (pinfunction "A_A") (pintype "passive"))
      (node (ref "D59") (pin "C") (pinfunction "C_C") (pintype "passive"))
      (node (ref "D60") (pin "A") (pinfunction "A_A") (pintype "passive"))
      (node (ref "D63") (pin "A") (pinfunction "A_A") (pintype "passive"))
      (node (ref "D90") (pin "A") (pinfunction "A_A") (pintype "passive"))
      (node (ref "Q8") (pin "3") (pinfunction "C_3") (pintype "passive"))
      (node (ref "R31") (pin "2") (pinfunction "2_2") (pintype "passive"))
    )
    (net (code "104") (name "Net-(Q9-B)") (class "Default")
      (node (ref "C12") (pin "1") (pinfunction "1_1") (pintype "passive"))
      (node (ref "D62") (pin "C") (pinfunction "C_C") (pintype "passive"))
      (node (ref "D70") (pin "C") (pinfunction "C_C") (pintype "passive"))
      (node (ref "Q9") (pin "2") (pinfunction "B_2") (pintype "passive"))
      (node (ref "R37") (pin "2") (pinfunction "2_2") (pintype "passive"))
    )
    (net (code "105") (name "Net-(Q9-C)") (class "Default")
      (node (ref "Q9") (pin "3") (pinfunction "C_3") (pintype "passive"))
      (node (ref "R33") (pin "2") (pinfunction "2_2") (pintype "passive"))
    )
    (net (code "106") (name "Net-(Q10-B)") (class "Default")
      (node (ref "D67") (pin "A") (pinfunction "A_A") (pintype "passive"))
      (node (ref "Q10") (pin "2") (pinfunction "B_2") (pintype "passive"))
      (node (ref "R39") (pin "1") (pinfunction "1_1") (pintype "passive"))
    )
    (net (code "107") (name "Net-(Q10-C)") (class "Default")
      (node (ref "Q10") (pin "3") (pinfunction "C_3") (pintype "passive"))
      (node (ref "Q5") (pin "1") (pinfunction "E_1") (pintype "passive"))
    )
    (net (code "108") (name "Net-(Q11-B)") (class "Default")
      (node (ref "D81") (pin "A") (pinfunction "A_A") (pintype "passive"))
      (node (ref "Q11") (pin "2") (pinfunction "B_2") (pintype "passive"))
      (node (ref "R46") (pin "1") (pinfunction "1_1") (pintype "passive"))
    )
    (net (code "109") (name "Net-(Q12-B)") (class "Default")
      (node (ref "D92") (pin "A") (pinfunction "A_A") (pintype "passive"))
      (node (ref "Q12") (pin "2") (pinfunction "B_2") (pintype "passive"))
      (node (ref "R51") (pin "1") (pinfunction "1_1") (pintype "passive"))
    )
  )
)
